# stm32-d40-platform.net
KiCad netlist of a schematic drawn in EAGLE
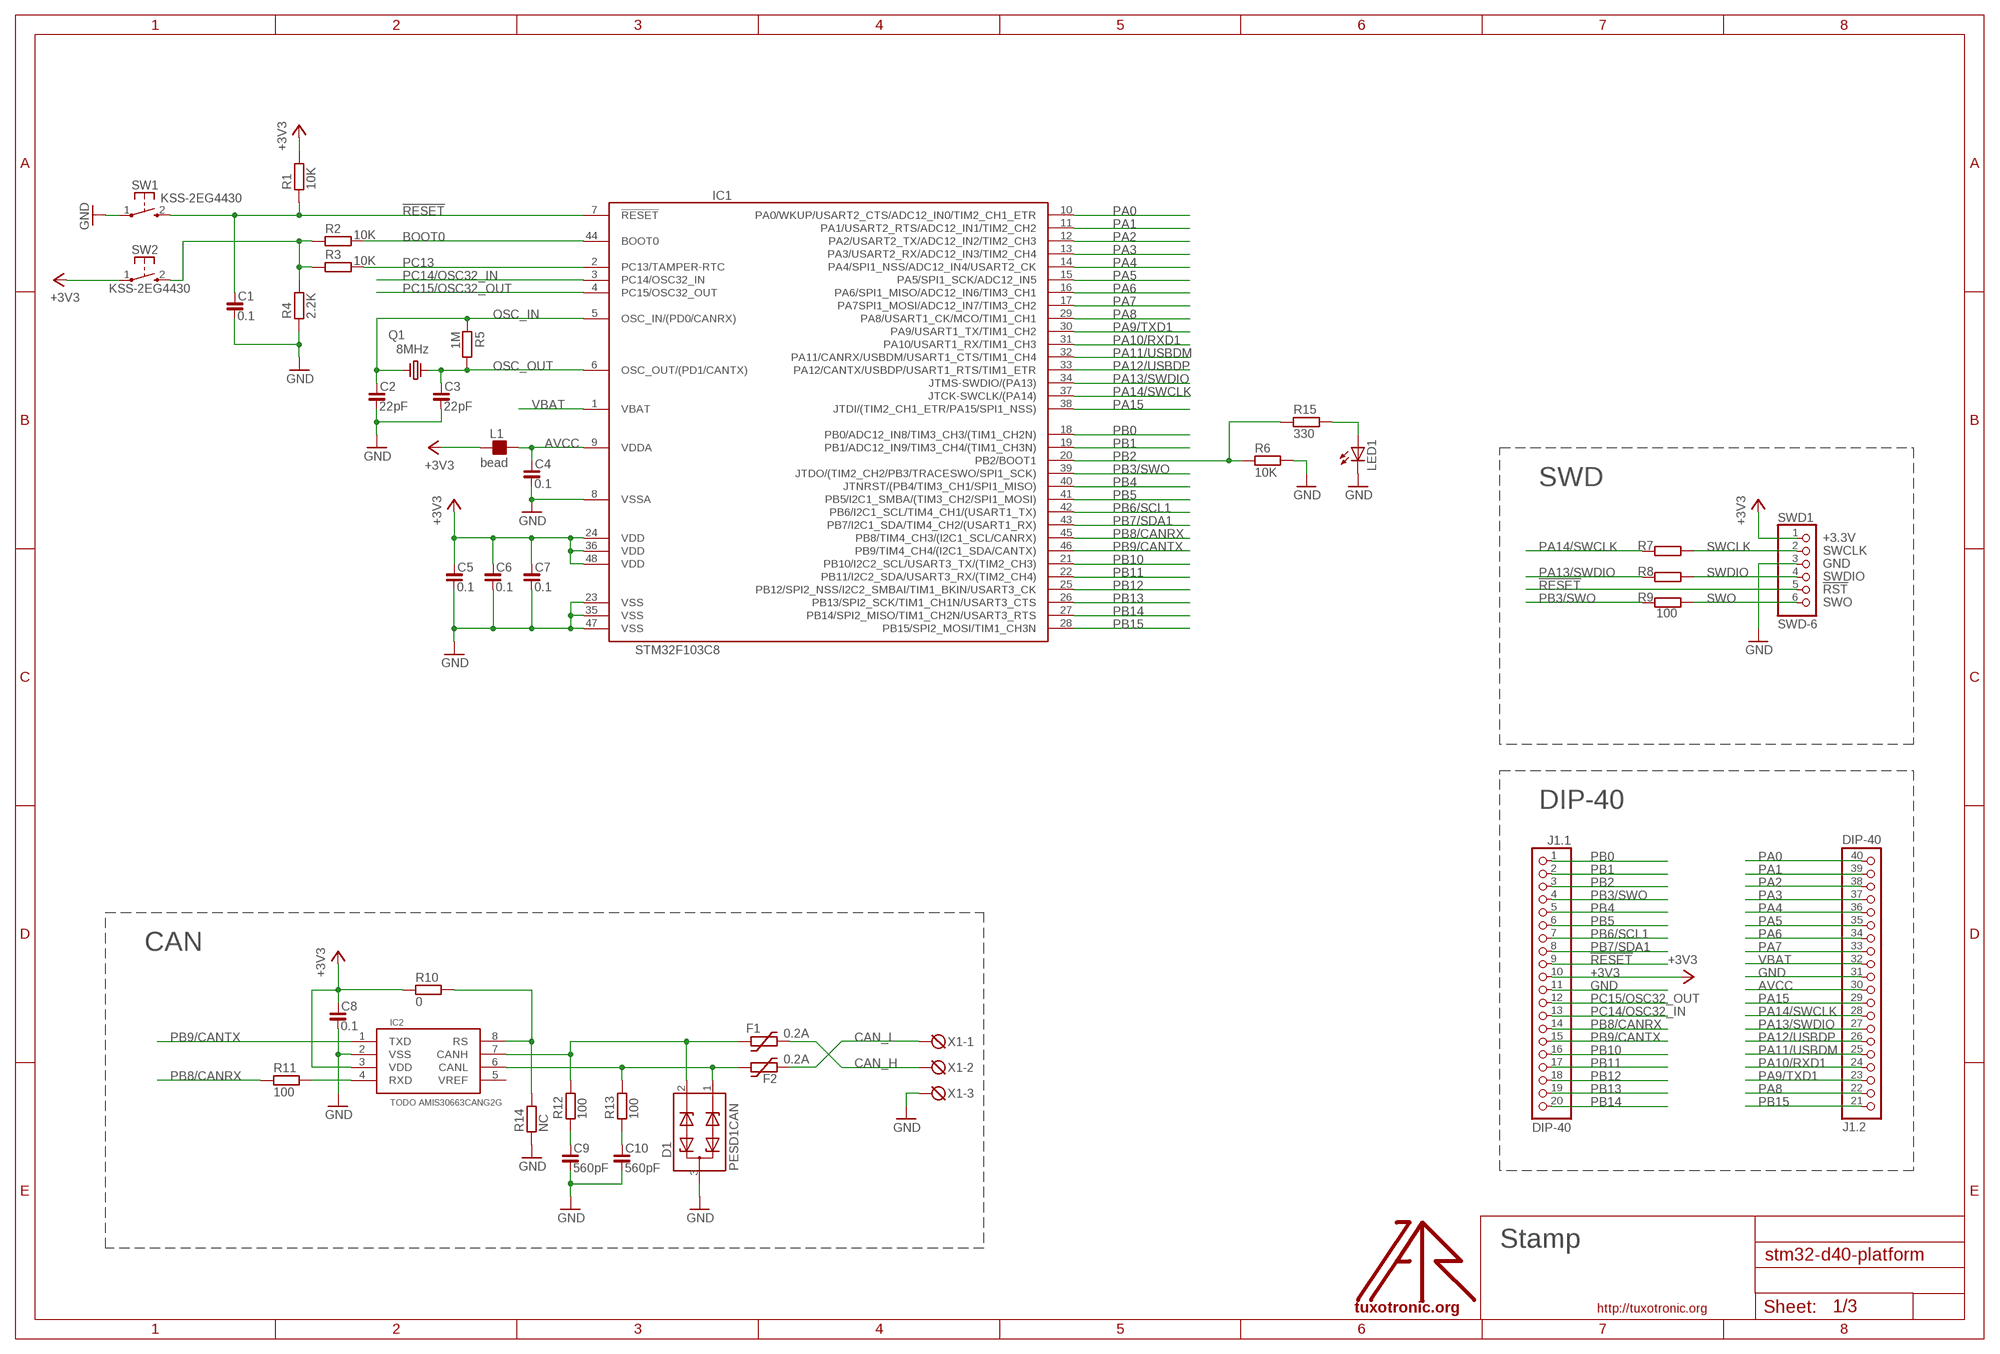
[diagram p0: schematic, sheet 1]
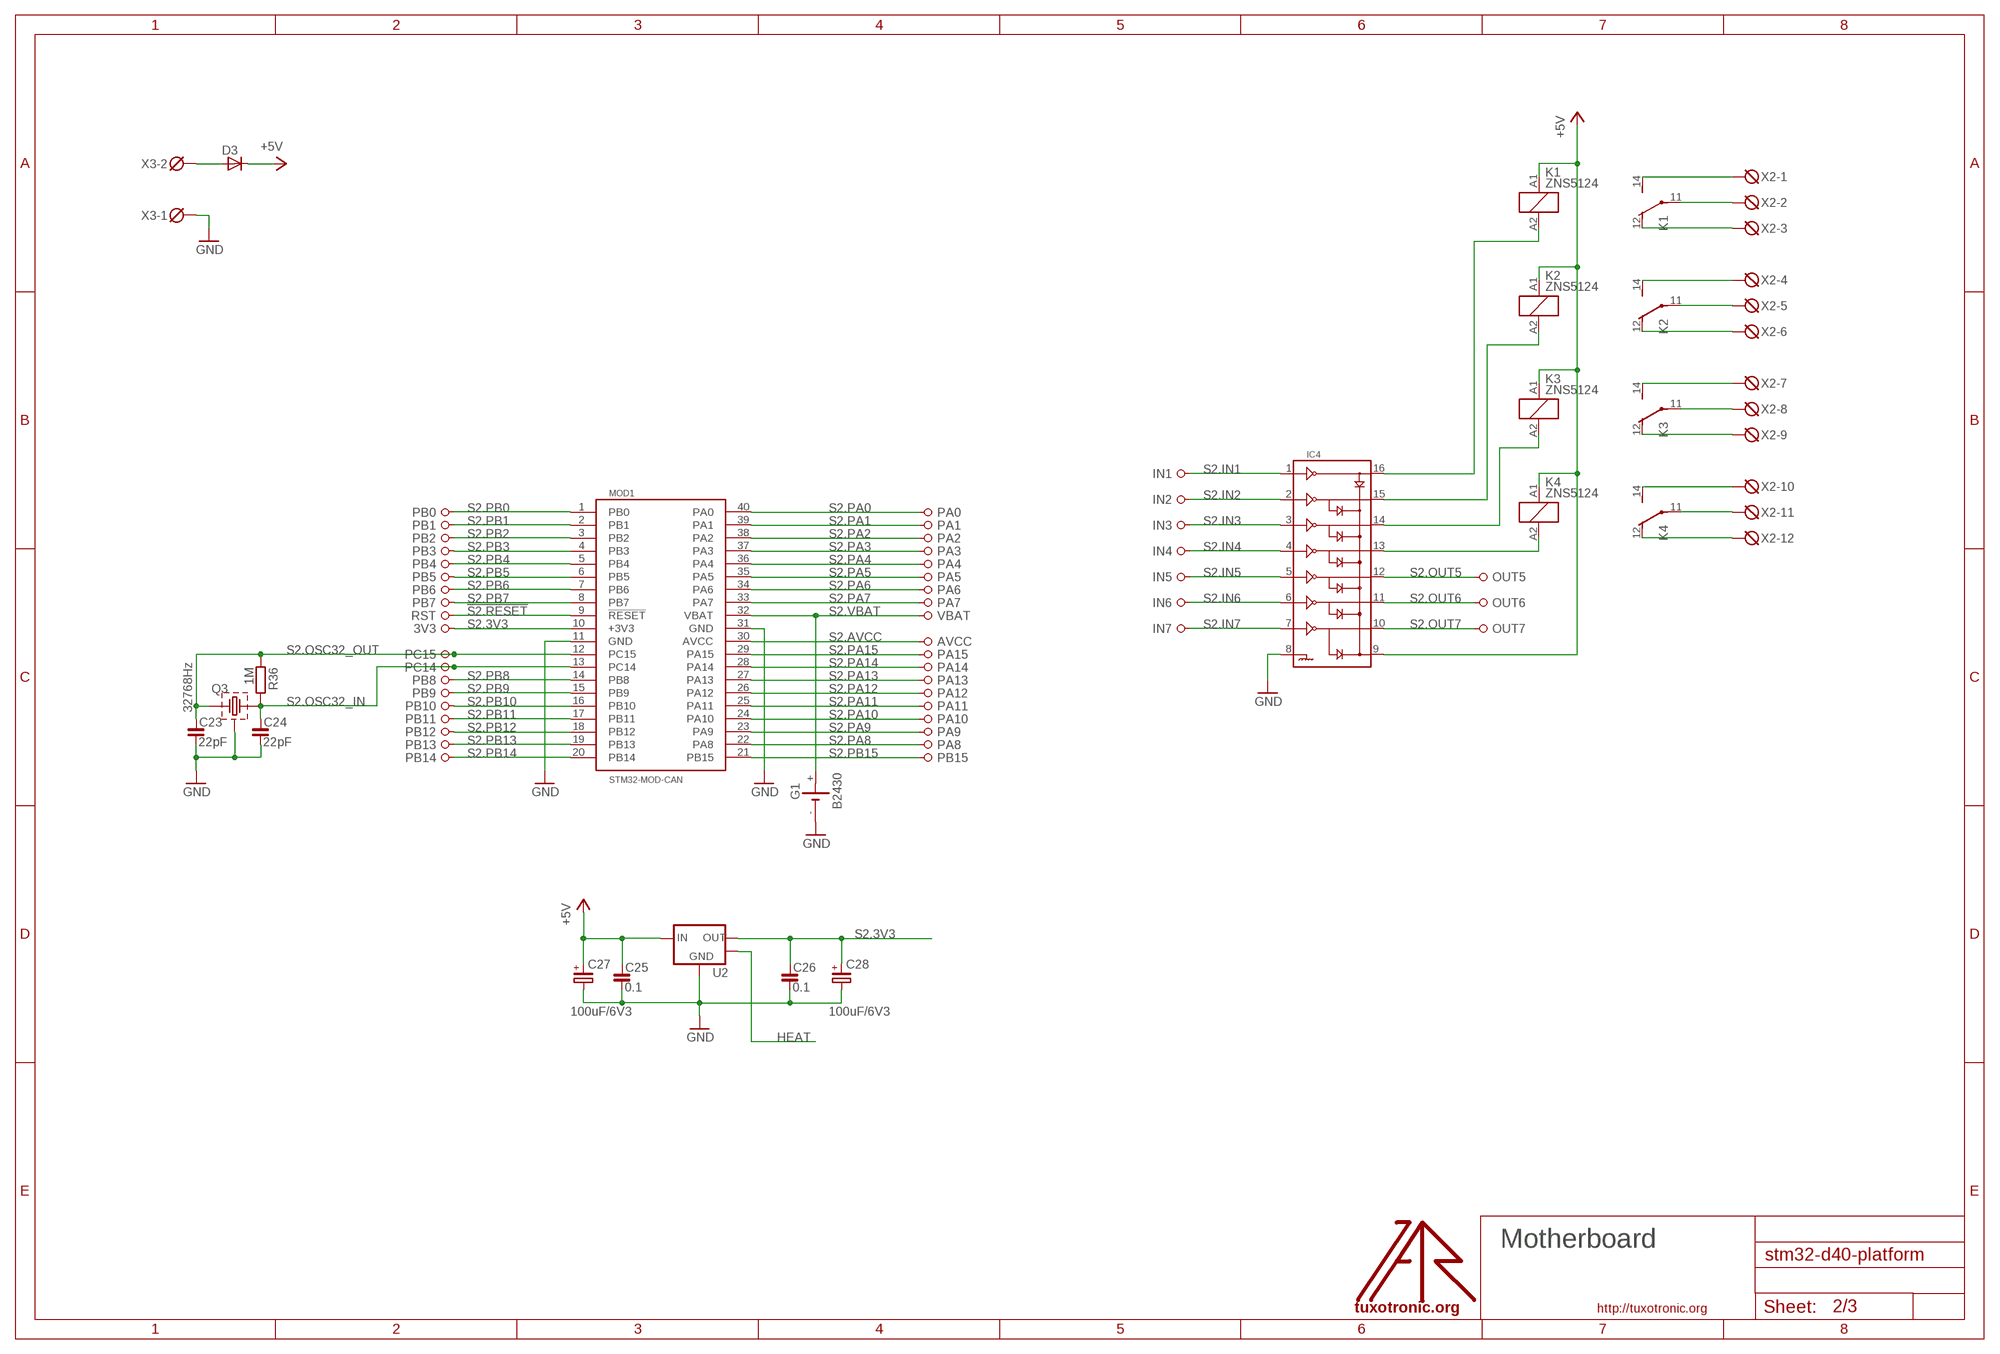
[diagram p1: schematic, sheet 2]
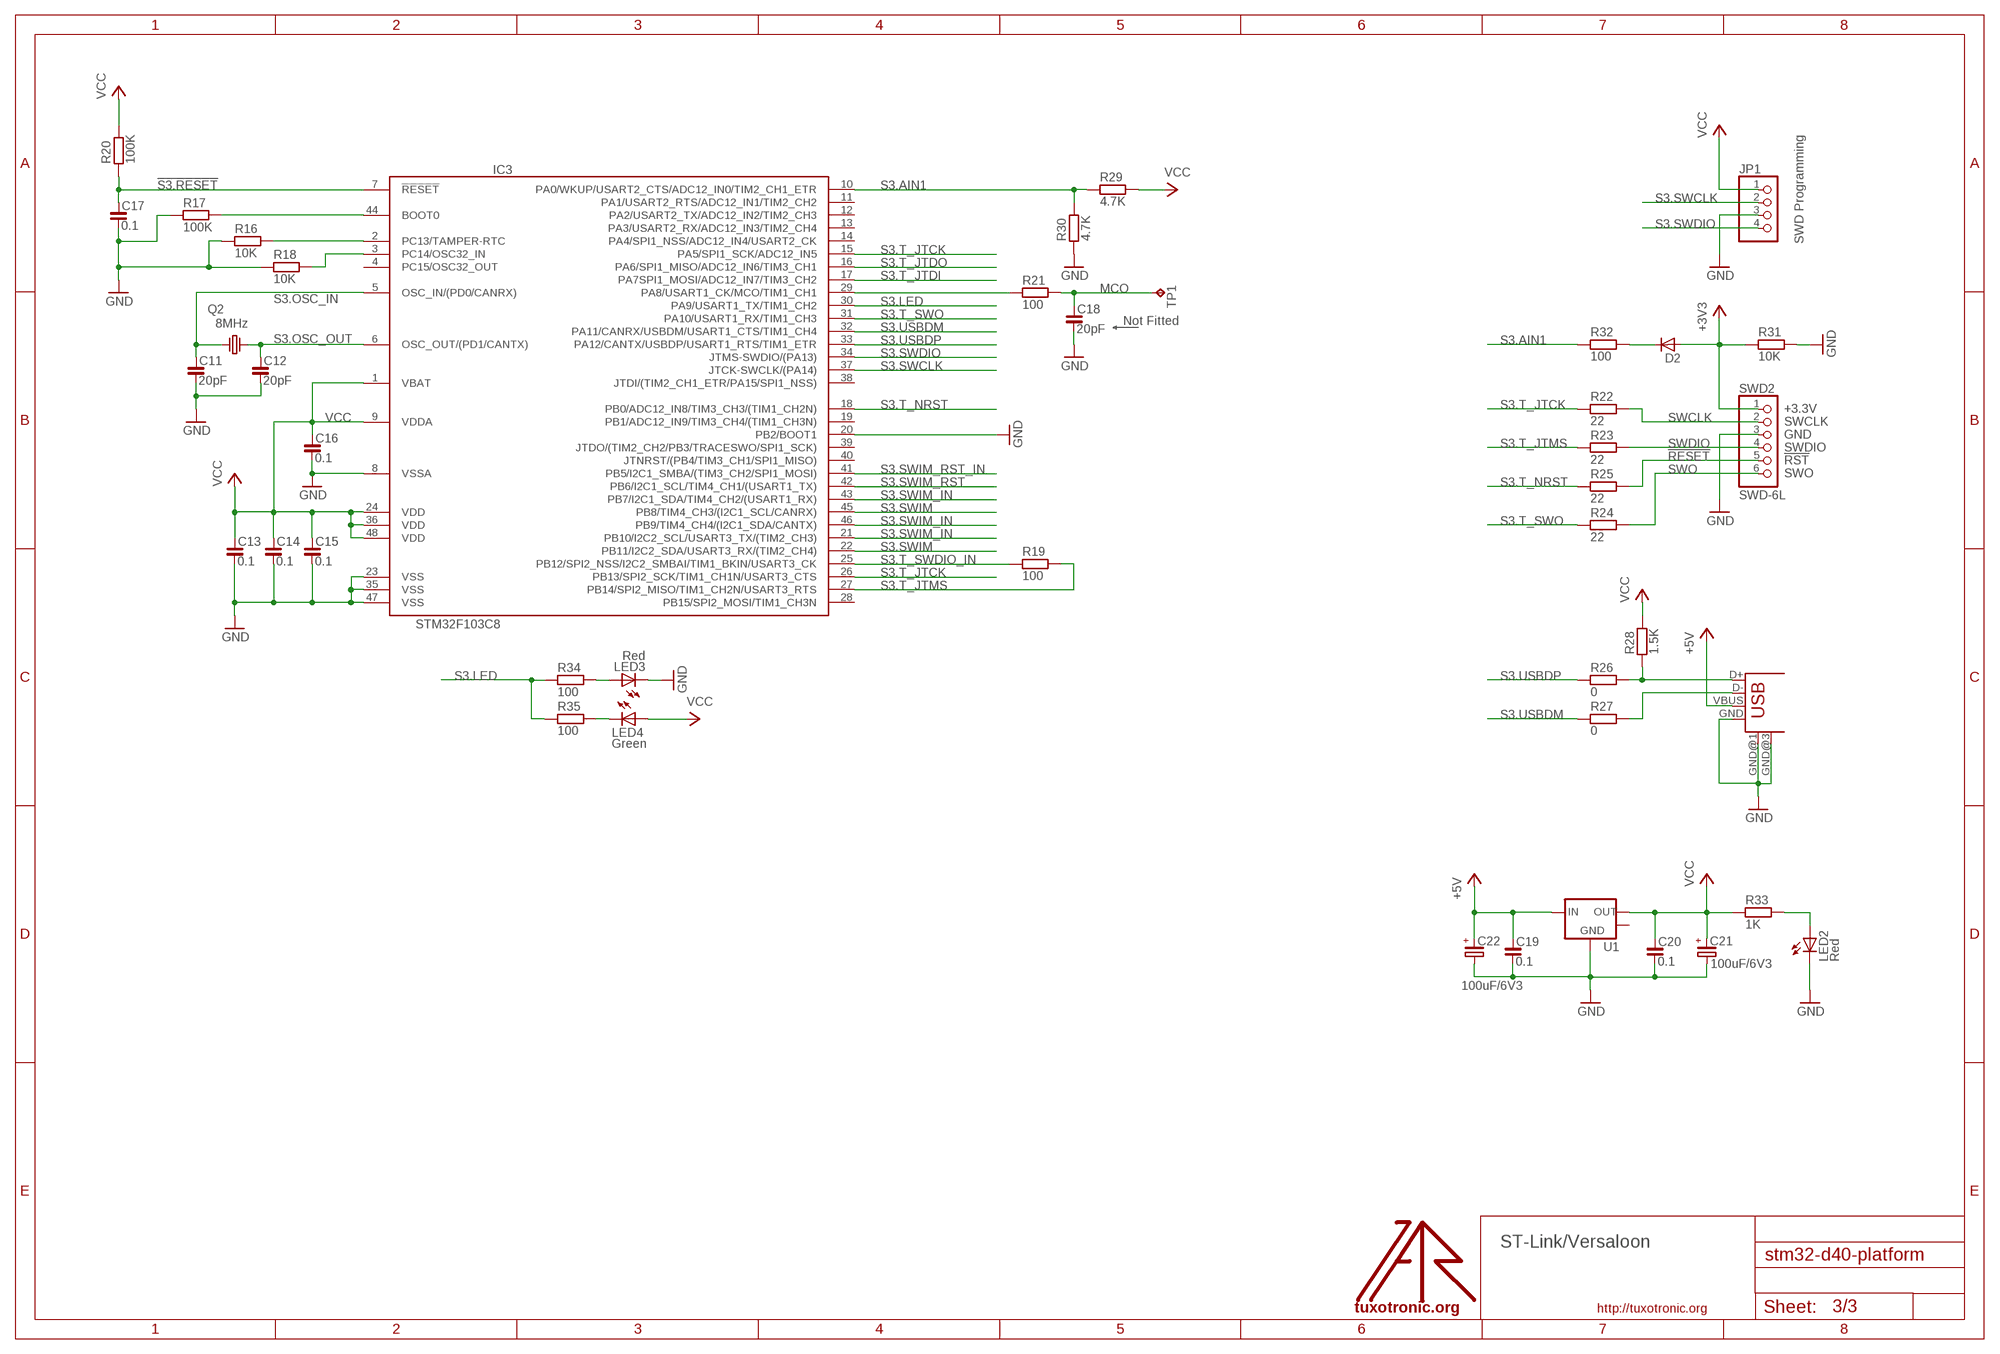
[diagram p2: schematic, sheet 3]

(export (version "E")
  (design (tool "Eeschema 10.0.6"))
  (components
    (comp (ref "C1")
      (value "0.1")
      (footprint "eagle-import:C0603")
      (libsource (lib "eagle-import") (part "C_0603"))
    )
    (comp (ref "C2")
      (value "22pF")
      (footprint "eagle-import:C0603")
      (libsource (lib "eagle-import") (part "C_0603"))
    )
    (comp (ref "C3")
      (value "22pF")
      (footprint "eagle-import:C0603")
      (libsource (lib "eagle-import") (part "C_0603"))
    )
    (comp (ref "C4")
      (value "0.1")
      (footprint "eagle-import:C0603")
      (libsource (lib "eagle-import") (part "C_0603"))
    )
    (comp (ref "C5")
      (value "0.1")
      (footprint "eagle-import:C0603")
      (libsource (lib "eagle-import") (part "C_0603"))
    )
    (comp (ref "C6")
      (value "0.1")
      (footprint "eagle-import:C0603")
      (libsource (lib "eagle-import") (part "C_0603"))
    )
    (comp (ref "C7")
      (value "0.1")
      (footprint "eagle-import:C0603")
      (libsource (lib "eagle-import") (part "C_0603"))
    )
    (comp (ref "C8")
      (value "0.1")
      (footprint "eagle-import:C0603")
      (libsource (lib "eagle-import") (part "C_0603"))
    )
    (comp (ref "C9")
      (value "560pF")
      (footprint "eagle-import:C0603")
      (libsource (lib "eagle-import") (part "C_0603"))
    )
    (comp (ref "C10")
      (value "560pF")
      (footprint "eagle-import:C0603")
      (libsource (lib "eagle-import") (part "C_0603"))
    )
    (comp (ref "D1")
      (value "PESD1CAN")
      (footprint "eagle-import:SOT23")
      (libsource (lib "eagle-import") (part "PESD1CAN"))
    )
    (comp (ref "F1")
      (value "0.2A")
      (footprint "eagle-import:1206L")
      (libsource (lib "eagle-import") (part "1206L"))
    )
    (comp (ref "F2")
      (value "0.2A")
      (footprint "eagle-import:1206L")
      (libsource (lib "eagle-import") (part "1206L"))
    )
    (comp (ref "IC1")
      (value "STM32F103C8")
      (footprint "eagle-import:LQFP48")
      (libsource (lib "eagle-import") (part "STM32F103C8"))
    )
    (comp (ref "IC2")
      (value "TODO AMIS30663CANG2G")
      (footprint "eagle-import:SO08")
      (libsource (lib "eagle-import") (part "SN65HVD230"))
    )
    (comp (ref "J1")
      (value "DIP-40")
      (footprint "eagle-import:DIP-40")
      (libsource (lib "eagle-import") (part "DIP-40"))
    )
    (comp (ref "L1")
      (value "bead")
      (footprint "eagle-import:L0603")
      (libsource (lib "eagle-import") (part "FB_0603"))
    )
    (comp (ref "LED1")
      (value "LEDCHIPLED_0603")
      (footprint "eagle-import:CHIPLED_0603")
      (libsource (lib "eagle-import") (part "LEDCHIPLED_0603"))
    )
    (comp (ref "Q1")
      (value "8MHz")
      (footprint "eagle-import:HC49_S")
      (libsource (lib "eagle-import") (part "CRYSTAL-HC49S"))
    )
    (comp (ref "R1")
      (value "10K")
      (footprint "eagle-import:R0603")
      (libsource (lib "eagle-import") (part "R_0603"))
    )
    (comp (ref "R2")
      (value "10K")
      (footprint "eagle-import:R0603")
      (libsource (lib "eagle-import") (part "R_0603"))
    )
    (comp (ref "R3")
      (value "10K")
      (footprint "eagle-import:R0603")
      (libsource (lib "eagle-import") (part "R_0603"))
    )
    (comp (ref "R4")
      (value "2.2K")
      (footprint "eagle-import:R0603")
      (libsource (lib "eagle-import") (part "R_0603"))
    )
    (comp (ref "R5")
      (value "1M")
      (footprint "eagle-import:R0603")
      (libsource (lib "eagle-import") (part "R_0603"))
    )
    (comp (ref "R6")
      (value "10K")
      (footprint "eagle-import:R0603")
      (libsource (lib "eagle-import") (part "R_0603"))
    )
    (comp (ref "R7")
      (value "100")
      (footprint "eagle-import:R0603")
      (libsource (lib "eagle-import") (part "R_0603"))
    )
    (comp (ref "R8")
      (value "100")
      (footprint "eagle-import:R0603")
      (libsource (lib "eagle-import") (part "R_0603"))
    )
    (comp (ref "R9")
      (value "100")
      (footprint "eagle-import:R0603")
      (libsource (lib "eagle-import") (part "R_0603"))
    )
    (comp (ref "R10")
      (value "0")
      (footprint "eagle-import:R0603")
      (libsource (lib "eagle-import") (part "R_0603"))
    )
    (comp (ref "R11")
      (value "100")
      (footprint "eagle-import:R0603")
      (libsource (lib "eagle-import") (part "R_0603"))
    )
    (comp (ref "R12")
      (value "100")
      (footprint "eagle-import:R0603")
      (libsource (lib "eagle-import") (part "R_0603"))
    )
    (comp (ref "R13")
      (value "100")
      (footprint "eagle-import:R0603")
      (libsource (lib "eagle-import") (part "R_0603"))
    )
    (comp (ref "R14")
      (value "NC")
      (footprint "eagle-import:R0603")
      (libsource (lib "eagle-import") (part "R_0603"))
    )
    (comp (ref "R15")
      (value "330")
      (footprint "eagle-import:R0603")
      (libsource (lib "eagle-import") (part "R_0603"))
    )
    (comp (ref "SW1")
      (value "KSS-2EG4430")
      (footprint "eagle-import:KSS-2EG4430")
      (libsource (lib "eagle-import") (part "KSS-2EG4430"))
    )
    (comp (ref "SW2")
      (value "KSS-2EG4430")
      (footprint "eagle-import:KSS-2EG4430")
      (libsource (lib "eagle-import") (part "KSS-2EG4430"))
    )
    (comp (ref "SWD1")
      (value "SWD-6")
      (footprint "eagle-import:JTAG6PIN")
      (libsource (lib "eagle-import") (part "SWD-6"))
    )
    (comp (ref "U$")
      (value "LOGO")
      (footprint "eagle-import:TT_LOGO")
      (libsource (lib "eagle-import") (part "LOGO"))
    )
    (comp (ref "X1")
      (value "DG3XX-03-3.5")
      (footprint "eagle-import:DG350-3.5-03P")
      (libsource (lib "eagle-import") (part "DG3XX-03-3.5"))
    )
    (comp (ref "3V3")
      (value "PIN-1X1_2.54")
      (footprint "eagle-import:1X01")
      (libsource (lib "eagle-import") (part "PIN-1X1_2.54"))
    )
    (comp (ref "AVCC")
      (value "PIN-1X1_2.54")
      (footprint "eagle-import:1X01")
      (libsource (lib "eagle-import") (part "PIN-1X1_2.54"))
    )
    (comp (ref "C23")
      (value "22pF")
      (footprint "eagle-import:C0805")
      (libsource (lib "eagle-import") (part "C_0805"))
    )
    (comp (ref "C24")
      (value "22pF")
      (footprint "eagle-import:C0805")
      (libsource (lib "eagle-import") (part "C_0805"))
    )
    (comp (ref "C25")
      (value "0.1")
      (footprint "eagle-import:C0805")
      (libsource (lib "eagle-import") (part "C_0805"))
    )
    (comp (ref "C26")
      (value "0.1")
      (footprint "eagle-import:C0805")
      (libsource (lib "eagle-import") (part "C_0805"))
    )
    (comp (ref "C27")
      (value "100uF/6V3")
      (footprint "eagle-import:CE-035X080")
      (libsource (lib "eagle-import") (part "CP_E-035X080"))
    )
    (comp (ref "C28")
      (value "100uF/6V3")
      (footprint "eagle-import:CE-035X080")
      (libsource (lib "eagle-import") (part "CP_E-035X080"))
    )
    (comp (ref "D3")
      (value "D-SMB")
      (footprint "eagle-import:SMB")
      (libsource (lib "eagle-import") (part "D-SMB"))
    )
    (comp (ref "G1")
      (value "B2430")
      (footprint "eagle-import:B2430")
      (libsource (lib "eagle-import") (part "B2430"))
    )
    (comp (ref "IC4")
      (value "ULN2003D")
      (footprint "eagle-import:SO16")
      (libsource (lib "eagle-import") (part "ULN2003D"))
    )
    (comp (ref "IN1")
      (value "PIN-1X1_2.54")
      (footprint "eagle-import:1X01")
      (libsource (lib "eagle-import") (part "PIN-1X1_2.54"))
    )
    (comp (ref "IN2")
      (value "PIN-1X1_2.54")
      (footprint "eagle-import:1X01")
      (libsource (lib "eagle-import") (part "PIN-1X1_2.54"))
    )
    (comp (ref "IN3")
      (value "PIN-1X1_2.54")
      (footprint "eagle-import:1X01")
      (libsource (lib "eagle-import") (part "PIN-1X1_2.54"))
    )
    (comp (ref "IN4")
      (value "PIN-1X1_2.54")
      (footprint "eagle-import:1X01")
      (libsource (lib "eagle-import") (part "PIN-1X1_2.54"))
    )
    (comp (ref "IN5")
      (value "PIN-1X1_2.54")
      (footprint "eagle-import:1X01")
      (libsource (lib "eagle-import") (part "PIN-1X1_2.54"))
    )
    (comp (ref "IN6")
      (value "PIN-1X1_2.54")
      (footprint "eagle-import:1X01")
      (libsource (lib "eagle-import") (part "PIN-1X1_2.54"))
    )
    (comp (ref "IN7")
      (value "PIN-1X1_2.54")
      (footprint "eagle-import:1X01")
      (libsource (lib "eagle-import") (part "PIN-1X1_2.54"))
    )
    (comp (ref "K1")
      (value "ZNS5124")
      (footprint "eagle-import:ZN5")
      (libsource (lib "eagle-import") (part "ZNS5124"))
    )
    (comp (ref "K2")
      (value "ZNS5124")
      (footprint "eagle-import:ZN5")
      (libsource (lib "eagle-import") (part "ZNS5124"))
    )
    (comp (ref "K3")
      (value "ZNS5124")
      (footprint "eagle-import:ZN5")
      (libsource (lib "eagle-import") (part "ZNS5124"))
    )
    (comp (ref "K4")
      (value "ZNS5124")
      (footprint "eagle-import:ZN5")
      (libsource (lib "eagle-import") (part "ZNS5124"))
    )
    (comp (ref "MOD1")
      (value "STM32-MOD-CAN")
      (footprint "eagle-import:DIL40")
      (libsource (lib "eagle-import") (part "STM32-MOD-CAN"))
    )
    (comp (ref "OUT5")
      (value "PIN-1X1_2.54")
      (footprint "eagle-import:1X01")
      (libsource (lib "eagle-import") (part "PIN-1X1_2.54"))
    )
    (comp (ref "OUT6")
      (value "PIN-1X1_2.54")
      (footprint "eagle-import:1X01")
      (libsource (lib "eagle-import") (part "PIN-1X1_2.54"))
    )
    (comp (ref "OUT7")
      (value "PIN-1X1_2.54")
      (footprint "eagle-import:1X01")
      (libsource (lib "eagle-import") (part "PIN-1X1_2.54"))
    )
    (comp (ref "PA0")
      (value "PIN-1X1_2.54")
      (footprint "eagle-import:1X01")
      (libsource (lib "eagle-import") (part "PIN-1X1_2.54"))
    )
    (comp (ref "PA1")
      (value "PIN-1X1_2.54")
      (footprint "eagle-import:1X01")
      (libsource (lib "eagle-import") (part "PIN-1X1_2.54"))
    )
    (comp (ref "PA2")
      (value "PIN-1X1_2.54")
      (footprint "eagle-import:1X01")
      (libsource (lib "eagle-import") (part "PIN-1X1_2.54"))
    )
    (comp (ref "PA3")
      (value "PIN-1X1_2.54")
      (footprint "eagle-import:1X01")
      (libsource (lib "eagle-import") (part "PIN-1X1_2.54"))
    )
    (comp (ref "PA4")
      (value "PIN-1X1_2.54")
      (footprint "eagle-import:1X01")
      (libsource (lib "eagle-import") (part "PIN-1X1_2.54"))
    )
    (comp (ref "PA5")
      (value "PIN-1X1_2.54")
      (footprint "eagle-import:1X01")
      (libsource (lib "eagle-import") (part "PIN-1X1_2.54"))
    )
    (comp (ref "PA6")
      (value "PIN-1X1_2.54")
      (footprint "eagle-import:1X01")
      (libsource (lib "eagle-import") (part "PIN-1X1_2.54"))
    )
    (comp (ref "PA7")
      (value "PIN-1X1_2.54")
      (footprint "eagle-import:1X01")
      (libsource (lib "eagle-import") (part "PIN-1X1_2.54"))
    )
    (comp (ref "PA8")
      (value "PIN-1X1_2.54")
      (footprint "eagle-import:1X01")
      (libsource (lib "eagle-import") (part "PIN-1X1_2.54"))
    )
    (comp (ref "PA9")
      (value "PIN-1X1_2.54")
      (footprint "eagle-import:1X01")
      (libsource (lib "eagle-import") (part "PIN-1X1_2.54"))
    )
    (comp (ref "PA10")
      (value "PIN-1X1_2.54")
      (footprint "eagle-import:1X01")
      (libsource (lib "eagle-import") (part "PIN-1X1_2.54"))
    )
    (comp (ref "PA11")
      (value "PIN-1X1_2.54")
      (footprint "eagle-import:1X01")
      (libsource (lib "eagle-import") (part "PIN-1X1_2.54"))
    )
    (comp (ref "PA12")
      (value "PIN-1X1_2.54")
      (footprint "eagle-import:1X01")
      (libsource (lib "eagle-import") (part "PIN-1X1_2.54"))
    )
    (comp (ref "PA13")
      (value "PIN-1X1_2.54")
      (footprint "eagle-import:1X01")
      (libsource (lib "eagle-import") (part "PIN-1X1_2.54"))
    )
    (comp (ref "PA14")
      (value "PIN-1X1_2.54")
      (footprint "eagle-import:1X01")
      (libsource (lib "eagle-import") (part "PIN-1X1_2.54"))
    )
    (comp (ref "PA15")
      (value "PIN-1X1_2.54")
      (footprint "eagle-import:1X01")
      (libsource (lib "eagle-import") (part "PIN-1X1_2.54"))
    )
    (comp (ref "PB0")
      (value "PIN-1X1_2.54")
      (footprint "eagle-import:1X01")
      (libsource (lib "eagle-import") (part "PIN-1X1_2.54"))
    )
    (comp (ref "PB1")
      (value "PIN-1X1_2.54")
      (footprint "eagle-import:1X01")
      (libsource (lib "eagle-import") (part "PIN-1X1_2.54"))
    )
    (comp (ref "PB2")
      (value "PIN-1X1_2.54")
      (footprint "eagle-import:1X01")
      (libsource (lib "eagle-import") (part "PIN-1X1_2.54"))
    )
    (comp (ref "PB3")
      (value "PIN-1X1_2.54")
      (footprint "eagle-import:1X01")
      (libsource (lib "eagle-import") (part "PIN-1X1_2.54"))
    )
    (comp (ref "PB4")
      (value "PIN-1X1_2.54")
      (footprint "eagle-import:1X01")
      (libsource (lib "eagle-import") (part "PIN-1X1_2.54"))
    )
    (comp (ref "PB5")
      (value "PIN-1X1_2.54")
      (footprint "eagle-import:1X01")
      (libsource (lib "eagle-import") (part "PIN-1X1_2.54"))
    )
    (comp (ref "PB6")
      (value "PIN-1X1_2.54")
      (footprint "eagle-import:1X01")
      (libsource (lib "eagle-import") (part "PIN-1X1_2.54"))
    )
    (comp (ref "PB7")
      (value "PIN-1X1_2.54")
      (footprint "eagle-import:1X01")
      (libsource (lib "eagle-import") (part "PIN-1X1_2.54"))
    )
    (comp (ref "PB8")
      (value "PIN-1X1_2.54")
      (footprint "eagle-import:1X01")
      (libsource (lib "eagle-import") (part "PIN-1X1_2.54"))
    )
    (comp (ref "PB9")
      (value "PIN-1X1_2.54")
      (footprint "eagle-import:1X01")
      (libsource (lib "eagle-import") (part "PIN-1X1_2.54"))
    )
    (comp (ref "PB10")
      (value "PIN-1X1_2.54")
      (footprint "eagle-import:1X01")
      (libsource (lib "eagle-import") (part "PIN-1X1_2.54"))
    )
    (comp (ref "PB11")
      (value "PIN-1X1_2.54")
      (footprint "eagle-import:1X01")
      (libsource (lib "eagle-import") (part "PIN-1X1_2.54"))
    )
    (comp (ref "PB12")
      (value "PIN-1X1_2.54")
      (footprint "eagle-import:1X01")
      (libsource (lib "eagle-import") (part "PIN-1X1_2.54"))
    )
    (comp (ref "PB13")
      (value "PIN-1X1_2.54")
      (footprint "eagle-import:1X01")
      (libsource (lib "eagle-import") (part "PIN-1X1_2.54"))
    )
    (comp (ref "PB14")
      (value "PIN-1X1_2.54")
      (footprint "eagle-import:1X01")
      (libsource (lib "eagle-import") (part "PIN-1X1_2.54"))
    )
    (comp (ref "PB15")
      (value "PIN-1X1_2.54")
      (footprint "eagle-import:1X01")
      (libsource (lib "eagle-import") (part "PIN-1X1_2.54"))
    )
    (comp (ref "PC14")
      (value "PIN-1X1_2.54")
      (footprint "eagle-import:1X01")
      (libsource (lib "eagle-import") (part "PIN-1X1_2.54"))
    )
    (comp (ref "PC15")
      (value "PIN-1X1_2.54")
      (footprint "eagle-import:1X01")
      (libsource (lib "eagle-import") (part "PIN-1X1_2.54"))
    )
    (comp (ref "Q3")
      (value "32768Hz")
      (footprint "eagle-import:TC38H-G")
      (libsource (lib "eagle-import") (part "CRSTL3-"))
    )
    (comp (ref "R36")
      (value "1M")
      (footprint "eagle-import:R0805")
      (libsource (lib "eagle-import") (part "R_0805"))
    )
    (comp (ref "RST")
      (value "PIN-1X1_2.54")
      (footprint "eagle-import:1X01")
      (libsource (lib "eagle-import") (part "PIN-1X1_2.54"))
    )
    (comp (ref "U$1")
      (value "LOGO")
      (footprint "eagle-import:TT_LOGO")
      (libsource (lib "eagle-import") (part "LOGO"))
    )
    (comp (ref "U2")
      (value "LM1117-3.3")
      (footprint "eagle-import:SOT223")
      (libsource (lib "eagle-import") (part "LM1117-3.3"))
    )
    (comp (ref "VBAT")
      (value "PIN-1X1_2.54")
      (footprint "eagle-import:1X01")
      (libsource (lib "eagle-import") (part "PIN-1X1_2.54"))
    )
    (comp (ref "X2")
      (value "DG3XX-12-5.0")
      (footprint "eagle-import:DG306-5.0-12P")
      (libsource (lib "eagle-import") (part "DG3XX-12-5.0"))
    )
    (comp (ref "X3")
      (value "DG3XX-02-5.0")
      (footprint "eagle-import:DG306-5.0-02P")
      (libsource (lib "eagle-import") (part "DG3XX-02-5.0"))
    )
    (comp (ref "C11")
      (value "20pF")
      (footprint "eagle-import:C0603")
      (libsource (lib "eagle-import") (part "C_0603"))
    )
    (comp (ref "C12")
      (value "20pF")
      (footprint "eagle-import:C0603")
      (libsource (lib "eagle-import") (part "C_0603"))
    )
    (comp (ref "C13")
      (value "0.1")
      (footprint "eagle-import:C0603")
      (libsource (lib "eagle-import") (part "C_0603"))
    )
    (comp (ref "C14")
      (value "0.1")
      (footprint "eagle-import:C0603")
      (libsource (lib "eagle-import") (part "C_0603"))
    )
    (comp (ref "C15")
      (value "0.1")
      (footprint "eagle-import:C0603")
      (libsource (lib "eagle-import") (part "C_0603"))
    )
    (comp (ref "C16")
      (value "0.1")
      (footprint "eagle-import:C0603")
      (libsource (lib "eagle-import") (part "C_0603"))
    )
    (comp (ref "C17")
      (value "0.1")
      (footprint "eagle-import:C0603")
      (libsource (lib "eagle-import") (part "C_0603"))
    )
    (comp (ref "C18")
      (value "20pF")
      (footprint "eagle-import:C0603")
      (libsource (lib "eagle-import") (part "C_0603"))
    )
    (comp (ref "C19")
      (value "0.1")
      (footprint "eagle-import:C0603")
      (libsource (lib "eagle-import") (part "C_0603"))
    )
    (comp (ref "C20")
      (value "0.1")
      (footprint "eagle-import:C0603")
      (libsource (lib "eagle-import") (part "C_0603"))
    )
    (comp (ref "C21")
      (value "100uF/6V3")
      (footprint "eagle-import:SMC_C")
      (libsource (lib "eagle-import") (part "CP_SMCC"))
    )
    (comp (ref "C22")
      (value "100uF/6V3")
      (footprint "eagle-import:SMC_C")
      (libsource (lib "eagle-import") (part "CP_SMCC"))
    )
    (comp (ref "D2")
      (value "BAT54A1-C3")
      (footprint "eagle-import:SOT23")
      (libsource (lib "eagle-import") (part "BAT54A1-C3"))
    )
    (comp (ref "IC3")
      (value "STM32F103C8")
      (footprint "eagle-import:LQFP48")
      (libsource (lib "eagle-import") (part "STM32F103C8"))
    )
    (comp (ref "JP1")
      (value "PINHD-1X4_2.00")
      (footprint "eagle-import:1X04M")
      (libsource (lib "eagle-import") (part "PINHD-1X4_2.00"))
    )
    (comp (ref "LED2")
      (value "Red")
      (footprint "eagle-import:CHIPLED_0603")
      (libsource (lib "eagle-import") (part "LEDCHIPLED_0603"))
    )
    (comp (ref "LED3")
      (value "Red")
      (footprint "eagle-import:CHIPLED_0603")
      (libsource (lib "eagle-import") (part "LEDCHIPLED_0603"))
    )
    (comp (ref "LED4")
      (value "Green")
      (footprint "eagle-import:CHIPLED_0603")
      (libsource (lib "eagle-import") (part "LEDCHIPLED_0603"))
    )
    (comp (ref "Q2")
      (value "8MHz")
      (footprint "eagle-import:HC49_S")
      (libsource (lib "eagle-import") (part "CRYSTAL-HC49S"))
    )
    (comp (ref "R16")
      (value "10K")
      (footprint "eagle-import:R0603")
      (libsource (lib "eagle-import") (part "R_0603"))
    )
    (comp (ref "R17")
      (value "100K")
      (footprint "eagle-import:R0603")
      (libsource (lib "eagle-import") (part "R_0603"))
    )
    (comp (ref "R18")
      (value "10K")
      (footprint "eagle-import:R0603")
      (libsource (lib "eagle-import") (part "R_0603"))
    )
    (comp (ref "R19")
      (value "100")
      (footprint "eagle-import:R0603")
      (libsource (lib "eagle-import") (part "R_0603"))
    )
    (comp (ref "R20")
      (value "100K")
      (footprint "eagle-import:R0603")
      (libsource (lib "eagle-import") (part "R_0603"))
    )
    (comp (ref "R21")
      (value "100")
      (footprint "eagle-import:R0603")
      (libsource (lib "eagle-import") (part "R_0603"))
    )
    (comp (ref "R22")
      (value "22")
      (footprint "eagle-import:R0603")
      (libsource (lib "eagle-import") (part "R_0603"))
    )
    (comp (ref "R23")
      (value "22")
      (footprint "eagle-import:R0603")
      (libsource (lib "eagle-import") (part "R_0603"))
    )
    (comp (ref "R24")
      (value "22")
      (footprint "eagle-import:R0603")
      (libsource (lib "eagle-import") (part "R_0603"))
    )
    (comp (ref "R25")
      (value "22")
      (footprint "eagle-import:R0603")
      (libsource (lib "eagle-import") (part "R_0603"))
    )
    (comp (ref "R26")
      (value "0")
      (footprint "eagle-import:R0603")
      (libsource (lib "eagle-import") (part "R_0603"))
    )
    (comp (ref "R27")
      (value "0")
      (footprint "eagle-import:R0603")
      (libsource (lib "eagle-import") (part "R_0603"))
    )
    (comp (ref "R28")
      (value "1.5K")
      (footprint "eagle-import:R0603")
      (libsource (lib "eagle-import") (part "R_0603"))
    )
    (comp (ref "R29")
      (value "4.7K")
      (footprint "eagle-import:R0603")
      (libsource (lib "eagle-import") (part "R_0603"))
    )
    (comp (ref "R30")
      (value "4.7K")
      (footprint "eagle-import:R0603")
      (libsource (lib "eagle-import") (part "R_0603"))
    )
    (comp (ref "R31")
      (value "10K")
      (footprint "eagle-import:R0603")
      (libsource (lib "eagle-import") (part "R_0603"))
    )
    (comp (ref "R32")
      (value "100")
      (footprint "eagle-import:R0603")
      (libsource (lib "eagle-import") (part "R_0603"))
    )
    (comp (ref "R33")
      (value "1K")
      (footprint "eagle-import:R0603")
      (libsource (lib "eagle-import") (part "R_0603"))
    )
    (comp (ref "R34")
      (value "100")
      (footprint "eagle-import:R0603")
      (libsource (lib "eagle-import") (part "R_0603"))
    )
    (comp (ref "R35")
      (value "100")
      (footprint "eagle-import:R0603")
      (libsource (lib "eagle-import") (part "R_0603"))
    )
    (comp (ref "S3.LOGO")
      (value "LOGO")
      (footprint "eagle-import:TT_LOGO")
      (libsource (lib "eagle-import") (part "LOGO"))
    )
    (comp (ref "SWD2")
      (value "SWD-6L")
      (footprint "eagle-import:SWD6PIN_L")
      (libsource (lib "eagle-import") (part "SWD-6L"))
    )
    (comp (ref "TP1")
      (value "TPB1,27")
      (footprint "eagle-import:B1,27")
      (libsource (lib "eagle-import") (part "TPB1,27"))
    )
    (comp (ref "U1")
      (value "LM1117-3.3")
      (footprint "eagle-import:SOT223")
      (libsource (lib "eagle-import") (part "LM1117-3.3"))
    )
    (comp (ref "USB1")
      (value "USB-MB-S2")
      (footprint "eagle-import:USB-MB-S2")
      (libsource (lib "eagle-import") (part "USB-MB-S2"))
    )
  )
  (nets
    (net (code "1") (name "+3V3") (class "Default")
      (node (ref "C5") (pin "1") (pinfunction "1_1") (pintype "passive"))
      (node (ref "C6") (pin "1") (pinfunction "1_1") (pintype "passive"))
      (node (ref "C7") (pin "1") (pinfunction "1_1") (pintype "passive"))
      (node (ref "C8") (pin "1") (pinfunction "1_1") (pintype "passive"))
      (node (ref "D2") (pin "1") (pinfunction "A_1") (pintype "passive"))
      (node (ref "IC1") (pin "24") (pinfunction "VDD_24") (pintype "power_in"))
      (node (ref "IC1") (pin "36") (pinfunction "VDD_36") (pintype "power_in"))
      (node (ref "IC1") (pin "48") (pinfunction "VDD_48") (pintype "power_in"))
      (node (ref "IC2") (pin "3") (pinfunction "VDD_3") (pintype "power_in"))
      (node (ref "J1") (pin "10") (pinfunction "10_10") (pintype "passive"))
      (node (ref "L1") (pin "1") (pinfunction "1_1") (pintype "passive"))
      (node (ref "R1") (pin "2") (pinfunction "2_2") (pintype "passive"))
      (node (ref "R10") (pin "1") (pinfunction "1_1") (pintype "passive"))
      (node (ref "R31") (pin "1") (pinfunction "1_1") (pintype "passive"))
      (node (ref "SW2") (pin "1") (pinfunction "P_1") (pintype "passive"))
      (node (ref "SWD1") (pin "1") (pinfunction "1_1") (pintype "passive"))
      (node (ref "SWD2") (pin "1") (pinfunction "1_1") (pintype "passive"))
    )
    (net (code "2") (name "+5V") (class "Default")
      (node (ref "C19") (pin "1") (pinfunction "1_1") (pintype "passive"))
      (node (ref "C22") (pin "+") (pinfunction "+_+") (pintype "passive"))
      (node (ref "C25") (pin "1") (pinfunction "1_1") (pintype "passive"))
      (node (ref "C27") (pin "+") (pinfunction "+_+") (pintype "passive"))
      (node (ref "D3") (pin "C") (pinfunction "C_C") (pintype "passive"))
      (node (ref "IC4") (pin "9") (pinfunction "9_9") (pintype "power_in"))
      (node (ref "K1") (pin "A1") (pinfunction "1_A1") (pintype "passive"))
      (node (ref "K2") (pin "A1") (pinfunction "1_A1") (pintype "passive"))
      (node (ref "K3") (pin "A1") (pinfunction "1_A1") (pintype "passive"))
      (node (ref "K4") (pin "A1") (pinfunction "1_A1") (pintype "passive"))
      (node (ref "U1") (pin "3") (pinfunction "IN_3") (pintype "power_in"))
      (node (ref "U2") (pin "3") (pinfunction "IN_3") (pintype "power_in"))
      (node (ref "USB1") (pin "VBUS") (pinfunction "VBUS_VBUS") (pintype "bidirectional"))
    )
    (net (code "3") (name "AVCC") (class "Default")
      (node (ref "C4") (pin "1") (pinfunction "1_1") (pintype "passive"))
      (node (ref "IC1") (pin "9") (pinfunction "VDDA_9") (pintype "power_in"))
      (node (ref "J1") (pin "30") (pinfunction "10_30") (pintype "passive"))
      (node (ref "L1") (pin "2") (pinfunction "2_2") (pintype "passive"))
    )
    (net (code "4") (name "BOOT0") (class "Default")
      (node (ref "IC1") (pin "44") (pinfunction "BOOT0_44") (pintype "input"))
      (node (ref "R2") (pin "2") (pinfunction "2_2") (pintype "passive"))
    )
    (net (code "5") (name "CAN_H") (class "Default")
      (node (ref "F1") (pin "P$2") (pinfunction "2_P$2") (pintype "passive"))
      (node (ref "X1") (pin "2") (pinfunction "KL_2") (pintype "passive"))
    )
    (net (code "6") (name "CAN_L") (class "Default")
      (node (ref "F2") (pin "P$2") (pinfunction "2_P$2") (pintype "passive"))
      (node (ref "X1") (pin "1") (pinfunction "KL_1") (pintype "passive"))
    )
    (net (code "7") (name "GND") (class "Default")
      (node (ref "C1") (pin "2") (pinfunction "2_2") (pintype "passive"))
      (node (ref "C10") (pin "2") (pinfunction "2_2") (pintype "passive"))
      (node (ref "C11") (pin "2") (pinfunction "2_2") (pintype "passive"))
      (node (ref "C12") (pin "2") (pinfunction "2_2") (pintype "passive"))
      (node (ref "C13") (pin "2") (pinfunction "2_2") (pintype "passive"))
      (node (ref "C14") (pin "2") (pinfunction "2_2") (pintype "passive"))
      (node (ref "C15") (pin "2") (pinfunction "2_2") (pintype "passive"))
      (node (ref "C16") (pin "2") (pinfunction "2_2") (pintype "passive"))
      (node (ref "C17") (pin "2") (pinfunction "2_2") (pintype "passive"))
      (node (ref "C18") (pin "2") (pinfunction "2_2") (pintype "passive"))
      (node (ref "C19") (pin "2") (pinfunction "2_2") (pintype "passive"))
      (node (ref "C2") (pin "2") (pinfunction "2_2") (pintype "passive"))
      (node (ref "C20") (pin "2") (pinfunction "2_2") (pintype "passive"))
      (node (ref "C21") (pin "-") (pinfunction "-_-") (pintype "passive"))
      (node (ref "C22") (pin "-") (pinfunction "-_-") (pintype "passive"))
      (node (ref "C23") (pin "2") (pinfunction "2_2") (pintype "passive"))
      (node (ref "C24") (pin "2") (pinfunction "2_2") (pintype "passive"))
      (node (ref "C25") (pin "2") (pinfunction "2_2") (pintype "passive"))
      (node (ref "C26") (pin "2") (pinfunction "2_2") (pintype "passive"))
      (node (ref "C27") (pin "-") (pinfunction "-_-") (pintype "passive"))
      (node (ref "C28") (pin "-") (pinfunction "-_-") (pintype "passive"))
      (node (ref "C3") (pin "2") (pinfunction "2_2") (pintype "passive"))
      (node (ref "C4") (pin "2") (pinfunction "2_2") (pintype "passive"))
      (node (ref "C5") (pin "2") (pinfunction "2_2") (pintype "passive"))
      (node (ref "C6") (pin "2") (pinfunction "2_2") (pintype "passive"))
      (node (ref "C7") (pin "2") (pinfunction "2_2") (pintype "passive"))
      (node (ref "C8") (pin "2") (pinfunction "2_2") (pintype "passive"))
      (node (ref "C9") (pin "2") (pinfunction "2_2") (pintype "passive"))
      (node (ref "D1") (pin "3") (pinfunction "3_3") (pintype "passive"))
      (node (ref "G1") (pin "-") (pinfunction "-_-") (pintype "passive"))
      (node (ref "IC1") (pin "23") (pinfunction "VSS_23") (pintype "power_in"))
      (node (ref "IC1") (pin "35") (pinfunction "VSS_35") (pintype "power_in"))
      (node (ref "IC1") (pin "47") (pinfunction "VSS_47") (pintype "power_in"))
      (node (ref "IC1") (pin "8") (pinfunction "VSSA_8") (pintype "power_in"))
      (node (ref "IC2") (pin "2") (pinfunction "VSS_2") (pintype "power_in"))
      (node (ref "IC3") (pin "20") (pinfunction "PB2/BOOT1_20") (pintype "bidirectional"))
      (node (ref "IC3") (pin "23") (pinfunction "VSS_23") (pintype "power_in"))
      (node (ref "IC3") (pin "35") (pinfunction "VSS_35") (pintype "power_in"))
      (node (ref "IC3") (pin "47") (pinfunction "VSS_47") (pintype "power_in"))
      (node (ref "IC3") (pin "8") (pinfunction "VSSA_8") (pintype "power_in"))
      (node (ref "IC4") (pin "8") (pinfunction "8_8") (pintype "power_in"))
      (node (ref "J1") (pin "11") (pinfunction "11_11") (pintype "passive"))
      (node (ref "J1") (pin "31") (pinfunction "11_31") (pintype "passive"))
      (node (ref "JP1") (pin "3") (pinfunction "3_3") (pintype "passive"))
      (node (ref "LED1") (pin "C") (pinfunction "C_C") (pintype "passive"))
      (node (ref "LED2") (pin "C") (pinfunction "C_C") (pintype "passive"))
      (node (ref "LED3") (pin "C") (pinfunction "C_C") (pintype "passive"))
      (node (ref "MOD1") (pin "11") (pinfunction "GND_11") (pintype "power_in"))
      (node (ref "MOD1") (pin "31") (pinfunction "GND_31") (pintype "power_in"))
      (node (ref "Q3") (pin "GND") (pinfunction "P$1_GND") (pintype "passive"))
      (node (ref "R14") (pin "1") (pinfunction "1_1") (pintype "passive"))
      (node (ref "R16") (pin "1") (pinfunction "1_1") (pintype "passive"))
      (node (ref "R17") (pin "1") (pinfunction "1_1") (pintype "passive"))
      (node (ref "R18") (pin "1") (pinfunction "1_1") (pintype "passive"))
      (node (ref "R30") (pin "1") (pinfunction "1_1") (pintype "passive"))
      (node (ref "R31") (pin "2") (pinfunction "2_2") (pintype "passive"))
      (node (ref "R4") (pin "1") (pinfunction "1_1") (pintype "passive"))
      (node (ref "R6") (pin "2") (pinfunction "2_2") (pintype "passive"))
      (node (ref "SW1") (pin "1") (pinfunction "P_1") (pintype "passive"))
      (node (ref "SWD1") (pin "3") (pinfunction "3_3") (pintype "passive"))
      (node (ref "SWD2") (pin "3") (pinfunction "3_3") (pintype "passive"))
      (node (ref "U1") (pin "1") (pinfunction "GND_1") (pintype "power_in"))
      (node (ref "U2") (pin "1") (pinfunction "GND_1") (pintype "power_in"))
      (node (ref "USB1") (pin "GND") (pinfunction "GND_GND") (pintype "bidirectional"))
      (node (ref "USB1") (pin "GND@1") (pinfunction "GND_GND@1") (pintype "bidirectional"))
      (node (ref "USB1") (pin "GND@3") (pinfunction "GND_GND@3") (pintype "bidirectional"))
      (node (ref "X1") (pin "3") (pinfunction "KL_3") (pintype "passive"))
      (node (ref "X3") (pin "1") (pinfunction "KL_1") (pintype "passive"))
    )
    (net (code "8") (name "HEAT") (class "Default")
      (node (ref "U2") (pin "4") (pinfunction "MASS_4") (pintype "passive"))
    )
    (net (code "9") (name "MCO") (class "Default")
      (node (ref "C18") (pin "1") (pinfunction "1_1") (pintype "passive"))
      (node (ref "R21") (pin "2") (pinfunction "2_2") (pintype "passive"))
      (node (ref "TP1") (pin "PP") (pinfunction "TP_PP") (pintype "input"))
    )
    (net (code "10") (name "Net-(C9-Pad1)") (class "Default")
      (node (ref "C9") (pin "1") (pinfunction "1_1") (pintype "passive"))
      (node (ref "R12") (pin "1") (pinfunction "1_1") (pintype "passive"))
    )
    (net (code "11") (name "Net-(C10-Pad1)") (class "Default")
      (node (ref "C10") (pin "1") (pinfunction "1_1") (pintype "passive"))
      (node (ref "R13") (pin "1") (pinfunction "1_1") (pintype "passive"))
    )
    (net (code "12") (name "Net-(D2-C)") (class "Default")
      (node (ref "D2") (pin "3") (pinfunction "C_3") (pintype "passive"))
      (node (ref "R32") (pin "2") (pinfunction "2_2") (pintype "passive"))
    )
    (net (code "13") (name "Net-(F1-1)") (class "Default")
      (node (ref "D1") (pin "2") (pinfunction "2_2") (pintype "passive"))
      (node (ref "F1") (pin "P$1") (pinfunction "1_P$1") (pintype "passive"))
      (node (ref "IC2") (pin "7") (pinfunction "CANH_7") (pintype "bidirectional"))
      (node (ref "R12") (pin "2") (pinfunction "2_2") (pintype "passive"))
    )
    (net (code "14") (name "Net-(F2-1)") (class "Default")
      (node (ref "D1") (pin "1") (pinfunction "1_1") (pintype "passive"))
      (node (ref "F2") (pin "P$1") (pinfunction "1_P$1") (pintype "passive"))
      (node (ref "IC2") (pin "6") (pinfunction "CANL_6") (pintype "bidirectional"))
      (node (ref "R13") (pin "2") (pinfunction "2_2") (pintype "passive"))
    )
    (net (code "15") (name "Net-(IC2-RS)") (class "Default")
      (node (ref "IC2") (pin "8") (pinfunction "RS_8") (pintype "input"))
      (node (ref "R10") (pin "2") (pinfunction "2_2") (pintype "passive"))
      (node (ref "R14") (pin "2") (pinfunction "2_2") (pintype "passive"))
    )
    (net (code "16") (name "Net-(IC2-RXD)") (class "Default")
      (node (ref "IC2") (pin "4") (pinfunction "RXD_4") (pintype "output"))
      (node (ref "R11") (pin "2") (pinfunction "2_2") (pintype "passive"))
    )
    (net (code "17") (name "Net-(IC3-BOOT0)") (class "Default")
      (node (ref "IC3") (pin "44") (pinfunction "BOOT0_44") (pintype "input"))
      (node (ref "R17") (pin "2") (pinfunction "2_2") (pintype "passive"))
    )
    (net (code "18") (name "Net-(IC3-PA8{slash}USART1_CK{slash}MCO{slash}TIM1_CH1)") (class "Default")
      (node (ref "IC3") (pin "29") (pinfunction "PA8/USART1_CK/MCO/TIM1_CH1_29") (pintype "bidirectional"))
      (node (ref "R21") (pin "1") (pinfunction "1_1") (pintype "passive"))
    )
    (net (code "19") (name "Net-(IC3-PC13{slash}TAMPER-RTC)") (class "Default")
      (node (ref "IC3") (pin "2") (pinfunction "PC13/TAMPER-RTC_2") (pintype "bidirectional"))
      (node (ref "R16") (pin "2") (pinfunction "2_2") (pintype "passive"))
    )
    (net (code "20") (name "Net-(IC3-PC14{slash}OSC32_IN)") (class "Default")
      (node (ref "IC3") (pin "3") (pinfunction "PC14/OSC32_IN_3") (pintype "bidirectional"))
      (node (ref "R18") (pin "2") (pinfunction "2_2") (pintype "passive"))
    )
    (net (code "21") (name "Net-(K1A-2)") (class "Default")
      (node (ref "IC4") (pin "16") (pinfunction "16_16") (pintype "open_collector"))
      (node (ref "K1") (pin "A2") (pinfunction "2_A2") (pintype "passive"))
    )
    (net (code "22") (name "Net-(K1B-O)") (class "Default")
      (node (ref "K1") (pin "12") (pinfunction "O_12") (pintype "passive"))
      (node (ref "X2") (pin "3") (pinfunction "KL_3") (pintype "passive"))
    )
    (net (code "23") (name "Net-(K1B-P)") (class "Default")
      (node (ref "K1") (pin "11") (pinfunction "P_11") (pintype "passive"))
      (node (ref "X2") (pin "2") (pinfunction "KL_2") (pintype "passive"))
    )
    (net (code "24") (name "Net-(K1B-S)") (class "Default")
      (node (ref "K1") (pin "14") (pinfunction "S_14") (pintype "passive"))
      (node (ref "X2") (pin "1") (pinfunction "KL_1") (pintype "passive"))
    )
    (net (code "25") (name "Net-(K2A-2)") (class "Default")
      (node (ref "IC4") (pin "15") (pinfunction "15_15") (pintype "open_collector"))
      (node (ref "K2") (pin "A2") (pinfunction "2_A2") (pintype "passive"))
    )
    (net (code "26") (name "Net-(K2B-O)") (class "Default")
      (node (ref "K2") (pin "12") (pinfunction "O_12") (pintype "passive"))
      (node (ref "X2") (pin "6") (pinfunction "KL_6") (pintype "passive"))
    )
    (net (code "27") (name "Net-(K2B-P)") (class "Default")
      (node (ref "K2") (pin "11") (pinfunction "P_11") (pintype "passive"))
      (node (ref "X2") (pin "5") (pinfunction "KL_5") (pintype "passive"))
    )
    (net (code "28") (name "Net-(K2B-S)") (class "Default")
      (node (ref "K2") (pin "14") (pinfunction "S_14") (pintype "passive"))
      (node (ref "X2") (pin "4") (pinfunction "KL_4") (pintype "passive"))
    )
    (net (code "29") (name "Net-(K3A-2)") (class "Default")
      (node (ref "IC4") (pin "14") (pinfunction "14_14") (pintype "open_collector"))
      (node (ref "K3") (pin "A2") (pinfunction "2_A2") (pintype "passive"))
    )
    (net (code "30") (name "Net-(K3B-O)") (class "Default")
      (node (ref "K3") (pin "12") (pinfunction "O_12") (pintype "passive"))
      (node (ref "X2") (pin "9") (pinfunction "KL_9") (pintype "passive"))
    )
    (net (code "31") (name "Net-(K3B-P)") (class "Default")
      (node (ref "K3") (pin "11") (pinfunction "P_11") (pintype "passive"))
      (node (ref "X2") (pin "8") (pinfunction "KL_8") (pintype "passive"))
    )
    (net (code "32") (name "Net-(K3B-S)") (class "Default")
      (node (ref "K3") (pin "14") (pinfunction "S_14") (pintype "passive"))
      (node (ref "X2") (pin "7") (pinfunction "KL_7") (pintype "passive"))
    )
    (net (code "33") (name "Net-(K4A-2)") (class "Default")
      (node (ref "IC4") (pin "13") (pinfunction "13_13") (pintype "open_collector"))
      (node (ref "K4") (pin "A2") (pinfunction "2_A2") (pintype "passive"))
    )
    (net (code "34") (name "Net-(K4B-O)") (class "Default")
      (node (ref "K4") (pin "12") (pinfunction "O_12") (pintype "passive"))
      (node (ref "X2") (pin "12") (pinfunction "KL_12") (pintype "passive"))
    )
    (net (code "35") (name "Net-(K4B-P)") (class "Default")
      (node (ref "K4") (pin "11") (pinfunction "P_11") (pintype "passive"))
      (node (ref "X2") (pin "11") (pinfunction "KL_11") (pintype "passive"))
    )
    (net (code "36") (name "Net-(K4B-S)") (class "Default")
      (node (ref "K4") (pin "14") (pinfunction "S_14") (pintype "passive"))
      (node (ref "X2") (pin "10") (pinfunction "KL_10") (pintype "passive"))
    )
    (net (code "37") (name "Net-(LED1-PadA)") (class "Default")
      (node (ref "LED1") (pin "A") (pinfunction "A_A") (pintype "passive"))
      (node (ref "R15") (pin "2") (pinfunction "2_2") (pintype "passive"))
    )
    (net (code "38") (name "Net-(LED2-PadA)") (class "Default")
      (node (ref "LED2") (pin "A") (pinfunction "A_A") (pintype "passive"))
      (node (ref "R33") (pin "2") (pinfunction "2_2") (pintype "passive"))
    )
    (net (code "39") (name "Net-(LED3-PadA)") (class "Default")
      (node (ref "LED3") (pin "A") (pinfunction "A_A") (pintype "passive"))
      (node (ref "R34") (pin "2") (pinfunction "2_2") (pintype "passive"))
    )
    (net (code "40") (name "Net-(LED4-PadC)") (class "Default")
      (node (ref "LED4") (pin "C") (pinfunction "C_C") (pintype "passive"))
      (node (ref "R35") (pin "2") (pinfunction "2_2") (pintype "passive"))
    )
    (net (code "41") (name "Net-(R26-Pad2)") (class "Default")
      (node (ref "R26") (pin "2") (pinfunction "2_2") (pintype "passive"))
      (node (ref "R28") (pin "1") (pinfunction "1_1") (pintype "passive"))
      (node (ref "USB1") (pin "D+") (pinfunction "D+_D+") (pintype "bidirectional"))
    )
    (net (code "42") (name "Net-(R27-Pad2)") (class "Default")
      (node (ref "R27") (pin "2") (pinfunction "2_2") (pintype "passive"))
      (node (ref "USB1") (pin "D-") (pinfunction "D-_D-") (pintype "bidirectional"))
    )
    (net (code "43") (name "Net-(SW2-S)") (class "Default")
      (node (ref "R2") (pin "1") (pinfunction "1_1") (pintype "passive"))
      (node (ref "R3") (pin "1") (pinfunction "1_1") (pintype "passive"))
      (node (ref "R4") (pin "2") (pinfunction "2_2") (pintype "passive"))
      (node (ref "SW2") (pin "2") (pinfunction "S_2") (pintype "passive"))
    )
    (net (code "44") (name "Net-(X3B-KL)") (class "Default")
      (node (ref "D3") (pin "A") (pinfunction "A_A") (pintype "passive"))
      (node (ref "X3") (pin "2") (pinfunction "KL_2") (pintype "passive"))
    )
    (net (code "45") (name "OSC_IN") (class "Default")
      (node (ref "C2") (pin "1") (pinfunction "1_1") (pintype "passive"))
      (node (ref "IC1") (pin "5") (pinfunction "OSC_IN/(PD0/CANRX)_5") (pintype "input"))
      (node (ref "Q1") (pin "1") (pinfunction "1_1") (pintype "passive"))
      (node (ref "R5") (pin "1") (pinfunction "1_1") (pintype "passive"))
    )
    (net (code "46") (name "OSC_OUT") (class "Default")
      (node (ref "C3") (pin "1") (pinfunction "1_1") (pintype "passive"))
      (node (ref "IC1") (pin "6") (pinfunction "OSC_OUT/(PD1/CANTX)_6") (pintype "output"))
      (node (ref "Q1") (pin "2") (pinfunction "2_2") (pintype "passive"))
      (node (ref "R5") (pin "2") (pinfunction "2_2") (pintype "passive"))
    )
    (net (code "47") (name "PA0") (class "Default")
      (node (ref "IC1") (pin "10") (pinfunction "PA0/WKUP/USART2_CTS/ADC12_IN0/TIM2_CH1_ETR_10") (pintype "bidirectional"))
      (node (ref "J1") (pin "40") (pinfunction "20_40") (pintype "passive"))
    )
    (net (code "48") (name "PA1") (class "Default")
      (node (ref "IC1") (pin "11") (pinfunction "PA1/USART2_RTS/ADC12_IN1/TIM2_CH2_11") (pintype "bidirectional"))
      (node (ref "J1") (pin "39") (pinfunction "19_39") (pintype "passive"))
    )
    (net (code "49") (name "PA2") (class "Default")
      (node (ref "IC1") (pin "12") (pinfunction "PA2/USART2_TX/ADC12_IN2/TIM2_CH3_12") (pintype "bidirectional"))
      (node (ref "J1") (pin "38") (pinfunction "18_38") (pintype "passive"))
    )
    (net (code "50") (name "PA3") (class "Default")
      (node (ref "IC1") (pin "13") (pinfunction "PA3/USART2_RX/ADC12_IN3/TIM2_CH4_13") (pintype "bidirectional"))
      (node (ref "J1") (pin "37") (pinfunction "17_37") (pintype "passive"))
    )
    (net (code "51") (name "PA4") (class "Default")
      (node (ref "IC1") (pin "14") (pinfunction "PA4/SPI1_NSS/ADC12_IN4/USART2_CK_14") (pintype "bidirectional"))
      (node (ref "J1") (pin "36") (pinfunction "16_36") (pintype "passive"))
    )
    (net (code "52") (name "PA5") (class "Default")
      (node (ref "IC1") (pin "15") (pinfunction "PA5/SPI1_SCK/ADC12_IN5_15") (pintype "bidirectional"))
      (node (ref "J1") (pin "35") (pinfunction "15_35") (pintype "passive"))
    )
    (net (code "53") (name "PA6") (class "Default")
      (node (ref "IC1") (pin "16") (pinfunction "PA6/SPI1_MISO/ADC12_IN6/TIM3_CH1_16") (pintype "bidirectional"))
      (node (ref "J1") (pin "34") (pinfunction "14_34") (pintype "passive"))
    )
    (net (code "54") (name "PA7") (class "Default")
      (node (ref "IC1") (pin "17") (pinfunction "PA7SPI1_MOSI/ADC12_IN7/TIM3_CH2_17") (pintype "bidirectional"))
      (node (ref "J1") (pin "33") (pinfunction "13_33") (pintype "passive"))
    )
    (net (code "55") (name "PA8") (class "Default")
      (node (ref "IC1") (pin "29") (pinfunction "PA8/USART1_CK/MCO/TIM1_CH1_29") (pintype "bidirectional"))
      (node (ref "J1") (pin "22") (pinfunction "2_22") (pintype "passive"))
    )
    (net (code "56") (name "PA9{slash}TXD1") (class "Default")
      (node (ref "IC1") (pin "30") (pinfunction "PA9/USART1_TX/TIM1_CH2_30") (pintype "bidirectional"))
      (node (ref "J1") (pin "23") (pinfunction "3_23") (pintype "passive"))
    )
    (net (code "57") (name "PA10{slash}RXD1") (class "Default")
      (node (ref "IC1") (pin "31") (pinfunction "PA10/USART1_RX/TIM1_CH3_31") (pintype "bidirectional"))
      (node (ref "J1") (pin "24") (pinfunction "4_24") (pintype "passive"))
    )
    (net (code "58") (name "PA11{slash}USBDM") (class "Default")
      (node (ref "IC1") (pin "32") (pinfunction "PA11/CANRX/USBDM/USART1_CTS/TIM1_CH4_32") (pintype "bidirectional"))
      (node (ref "J1") (pin "25") (pinfunction "5_25") (pintype "passive"))
    )
    (net (code "59") (name "PA12{slash}USBDP") (class "Default")
      (node (ref "IC1") (pin "33") (pinfunction "PA12/CANTX/USBDP/USART1_RTS/TIM1_ETR_33") (pintype "bidirectional"))
      (node (ref "J1") (pin "26") (pinfunction "6_26") (pintype "passive"))
    )
    (net (code "60") (name "PA13{slash}SWDIO") (class "Default")
      (node (ref "IC1") (pin "34") (pinfunction "JTMS-SWDIO/(PA13)_34") (pintype "bidirectional"))
      (node (ref "J1") (pin "27") (pinfunction "7_27") (pintype "passive"))
      (node (ref "R8") (pin "1") (pinfunction "1_1") (pintype "passive"))
    )
    (net (code "61") (name "PA14{slash}SWCLK") (class "Default")
      (node (ref "IC1") (pin "37") (pinfunction "JTCK-SWCLK/(PA14)_37") (pintype "bidirectional"))
      (node (ref "J1") (pin "28") (pinfunction "8_28") (pintype "passive"))
      (node (ref "R7") (pin "1") (pinfunction "1_1") (pintype "passive"))
    )
    (net (code "62") (name "PA15") (class "Default")
      (node (ref "IC1") (pin "38") (pinfunction "JTDI/(TIM2_CH1_ETR/PA15/SPI1_NSS)_38") (pintype "bidirectional"))
      (node (ref "J1") (pin "29") (pinfunction "9_29") (pintype "passive"))
    )
    (net (code "63") (name "PB0") (class "Default")
      (node (ref "IC1") (pin "18") (pinfunction "PB0/ADC12_IN8/TIM3_CH3/(TIM1_CH2N)_18") (pintype "bidirectional"))
      (node (ref "J1") (pin "1") (pinfunction "1_1") (pintype "passive"))
    )
    (net (code "64") (name "PB1") (class "Default")
      (node (ref "IC1") (pin "19") (pinfunction "PB1/ADC12_IN9/TIM3_CH4/(TIM1_CH3N)_19") (pintype "bidirectional"))
      (node (ref "J1") (pin "2") (pinfunction "2_2") (pintype "passive"))
    )
    (net (code "65") (name "PB2") (class "Default")
      (node (ref "IC1") (pin "20") (pinfunction "PB2/BOOT1_20") (pintype "bidirectional"))
      (node (ref "J1") (pin "3") (pinfunction "3_3") (pintype "passive"))
      (node (ref "R15") (pin "1") (pinfunction "1_1") (pintype "passive"))
      (node (ref "R6") (pin "1") (pinfunction "1_1") (pintype "passive"))
    )
    (net (code "66") (name "PB3{slash}SWO") (class "Default")
      (node (ref "IC1") (pin "39") (pinfunction "JTDO/(TIM2_CH2/PB3/TRACESWO/SPI1_SCK)_39") (pintype "bidirectional"))
      (node (ref "J1") (pin "4") (pinfunction "4_4") (pintype "passive"))
      (node (ref "R9") (pin "1") (pinfunction "1_1") (pintype "passive"))
    )
    (net (code "67") (name "PB4") (class "Default")
      (node (ref "IC1") (pin "40") (pinfunction "JTNRST/(PB4/TIM3_CH1/SPI1_MISO)_40") (pintype "bidirectional"))
      (node (ref "J1") (pin "5") (pinfunction "5_5") (pintype "passive"))
    )
    (net (code "68") (name "PB5") (class "Default")
      (node (ref "IC1") (pin "41") (pinfunction "PB5/I2C1_SMBA/(TIM3_CH2/SPI1_MOSI)_41") (pintype "bidirectional"))
      (node (ref "J1") (pin "6") (pinfunction "6_6") (pintype "passive"))
    )
    (net (code "69") (name "PB6{slash}SCL1") (class "Default")
      (node (ref "IC1") (pin "42") (pinfunction "PB6/I2C1_SCL/TIM4_CH1/(USART1_TX)_42") (pintype "bidirectional"))
      (node (ref "J1") (pin "7") (pinfunction "7_7") (pintype "passive"))
    )
    (net (code "70") (name "PB7{slash}SDA1") (class "Default")
      (node (ref "IC1") (pin "43") (pinfunction "PB7/I2C1_SDA/TIM4_CH2/(USART1_RX)_43") (pintype "bidirectional"))
      (node (ref "J1") (pin "8") (pinfunction "8_8") (pintype "passive"))
    )
    (net (code "71") (name "PB8{slash}CANRX") (class "Default")
      (node (ref "IC1") (pin "45") (pinfunction "PB8/TIM4_CH3/(I2C1_SCL/CANRX)_45") (pintype "bidirectional"))
      (node (ref "J1") (pin "14") (pinfunction "14_14") (pintype "passive"))
      (node (ref "R11") (pin "1") (pinfunction "1_1") (pintype "passive"))
    )
    (net (code "72") (name "PB9{slash}CANTX") (class "Default")
      (node (ref "IC1") (pin "46") (pinfunction "PB9/TIM4_CH4/(I2C1_SDA/CANTX)_46") (pintype "bidirectional"))
      (node (ref "IC2") (pin "1") (pinfunction "TXD_1") (pintype "input"))
      (node (ref "J1") (pin "15") (pinfunction "15_15") (pintype "passive"))
    )
    (net (code "73") (name "PB10") (class "Default")
      (node (ref "IC1") (pin "21") (pinfunction "PB10/I2C2_SCL/USART3_TX/(TIM2_CH3)_21") (pintype "bidirectional"))
      (node (ref "J1") (pin "16") (pinfunction "16_16") (pintype "passive"))
    )
    (net (code "74") (name "PB11") (class "Default")
      (node (ref "IC1") (pin "22") (pinfunction "PB11/I2C2_SDA/USART3_RX/(TIM2_CH4)_22") (pintype "bidirectional"))
      (node (ref "J1") (pin "17") (pinfunction "17_17") (pintype "passive"))
    )
    (net (code "75") (name "PB12") (class "Default")
      (node (ref "IC1") (pin "25") (pinfunction "PB12/SPI2_NSS/I2C2_SMBAI/TIM1_BKIN/USART3_CK_25") (pintype "bidirectional"))
      (node (ref "J1") (pin "18") (pinfunction "18_18") (pintype "passive"))
    )
    (net (code "76") (name "PB13") (class "Default")
      (node (ref "IC1") (pin "26") (pinfunction "PB13/SPI2_SCK/TIM1_CH1N/USART3_CTS_26") (pintype "bidirectional"))
      (node (ref "J1") (pin "19") (pinfunction "19_19") (pintype "passive"))
    )
    (net (code "77") (name "PB14") (class "Default")
      (node (ref "IC1") (pin "27") (pinfunction "PB14/SPI2_MISO/TIM1_CH2N/USART3_RTS_27") (pintype "bidirectional"))
      (node (ref "J1") (pin "20") (pinfunction "20_20") (pintype "passive"))
    )
    (net (code "78") (name "PB15") (class "Default")
      (node (ref "IC1") (pin "28") (pinfunction "PB15/SPI2_MOSI/TIM1_CH3N_28") (pintype "bidirectional"))
      (node (ref "J1") (pin "21") (pinfunction "1_21") (pintype "passive"))
    )
    (net (code "79") (name "PC13") (class "Default")
      (node (ref "IC1") (pin "2") (pinfunction "PC13/TAMPER-RTC_2") (pintype "bidirectional"))
      (node (ref "R3") (pin "2") (pinfunction "2_2") (pintype "passive"))
    )
    (net (code "80") (name "PC14{slash}OSC32_IN") (class "Default")
      (node (ref "IC1") (pin "3") (pinfunction "PC14/OSC32_IN_3") (pintype "bidirectional"))
      (node (ref "J1") (pin "13") (pinfunction "13_13") (pintype "passive"))
    )
    (net (code "81") (name "PC15{slash}OSC32_OUT") (class "Default")
      (node (ref "IC1") (pin "4") (pinfunction "PC15/OSC32_OUT_4") (pintype "bidirectional"))
      (node (ref "J1") (pin "12") (pinfunction "12_12") (pintype "passive"))
    )
    (net (code "82") (name "S2.3V3") (class "Default")
      (node (ref "3V3") (pin "1") (pinfunction "1_1") (pintype "passive"))
      (node (ref "C26") (pin "1") (pinfunction "1_1") (pintype "passive"))
      (node (ref "C28") (pin "+") (pinfunction "+_+") (pintype "passive"))
      (node (ref "MOD1") (pin "10") (pinfunction "+3V3_10") (pintype "power_in"))
      (node (ref "U2") (pin "2") (pinfunction "OUT_2") (pintype "power_in"))
    )
    (net (code "83") (name "S2.AVCC") (class "Default")
      (node (ref "AVCC") (pin "1") (pinfunction "1_1") (pintype "passive"))
      (node (ref "MOD1") (pin "30") (pinfunction "AVCC_30") (pintype "power_in"))
    )
    (net (code "84") (name "S2.IN1") (class "Default")
      (node (ref "IC4") (pin "1") (pinfunction "1_1") (pintype "input"))
      (node (ref "IN1") (pin "1") (pinfunction "1_1") (pintype "passive"))
    )
    (net (code "85") (name "S2.IN2") (class "Default")
      (node (ref "IC4") (pin "2") (pinfunction "2_2") (pintype "input"))
      (node (ref "IN2") (pin "1") (pinfunction "1_1") (pintype "passive"))
    )
    (net (code "86") (name "S2.IN3") (class "Default")
      (node (ref "IC4") (pin "3") (pinfunction "3_3") (pintype "input"))
      (node (ref "IN3") (pin "1") (pinfunction "1_1") (pintype "passive"))
    )
    (net (code "87") (name "S2.IN4") (class "Default")
      (node (ref "IC4") (pin "4") (pinfunction "4_4") (pintype "input"))
      (node (ref "IN4") (pin "1") (pinfunction "1_1") (pintype "passive"))
    )
    (net (code "88") (name "S2.IN5") (class "Default")
      (node (ref "IC4") (pin "5") (pinfunction "5_5") (pintype "input"))
      (node (ref "IN5") (pin "1") (pinfunction "1_1") (pintype "passive"))
    )
    (net (code "89") (name "S2.IN6") (class "Default")
      (node (ref "IC4") (pin "6") (pinfunction "6_6") (pintype "input"))
      (node (ref "IN6") (pin "1") (pinfunction "1_1") (pintype "passive"))
    )
    (net (code "90") (name "S2.IN7") (class "Default")
      (node (ref "IC4") (pin "7") (pinfunction "7_7") (pintype "input"))
      (node (ref "IN7") (pin "1") (pinfunction "1_1") (pintype "passive"))
    )
    (net (code "91") (name "S2.OSC32_IN") (class "Default")
      (node (ref "C24") (pin "1") (pinfunction "1_1") (pintype "passive"))
      (node (ref "MOD1") (pin "13") (pinfunction "PC14_13") (pintype "bidirectional"))
      (node (ref "PC14") (pin "1") (pinfunction "1_1") (pintype "passive"))
      (node (ref "Q3") (pin "2") (pinfunction "2_2") (pintype "passive"))
      (node (ref "R36") (pin "2") (pinfunction "2_2") (pintype "passive"))
    )
    (net (code "92") (name "S2.OSC32_OUT") (class "Default")
      (node (ref "C23") (pin "1") (pinfunction "1_1") (pintype "passive"))
      (node (ref "MOD1") (pin "12") (pinfunction "PC15_12") (pintype "bidirectional"))
      (node (ref "PC15") (pin "1") (pinfunction "1_1") (pintype "passive"))
      (node (ref "Q3") (pin "1") (pinfunction "1_1") (pintype "passive"))
      (node (ref "R36") (pin "1") (pinfunction "1_1") (pintype "passive"))
    )
    (net (code "93") (name "S2.OUT5") (class "Default")
      (node (ref "IC4") (pin "12") (pinfunction "12_12") (pintype "open_collector"))
      (node (ref "OUT5") (pin "1") (pinfunction "1_1") (pintype "passive"))
    )
    (net (code "94") (name "S2.OUT6") (class "Default")
      (node (ref "IC4") (pin "11") (pinfunction "11_11") (pintype "open_collector"))
      (node (ref "OUT6") (pin "1") (pinfunction "1_1") (pintype "passive"))
    )
    (net (code "95") (name "S2.OUT7") (class "Default")
      (node (ref "IC4") (pin "10") (pinfunction "10_10") (pintype "open_collector"))
      (node (ref "OUT7") (pin "1") (pinfunction "1_1") (pintype "passive"))
    )
    (net (code "96") (name "S2.PA0") (class "Default")
      (node (ref "MOD1") (pin "40") (pinfunction "PA0_40") (pintype "bidirectional"))
      (node (ref "PA0") (pin "1") (pinfunction "1_1") (pintype "passive"))
    )
    (net (code "97") (name "S2.PA1") (class "Default")
      (node (ref "MOD1") (pin "39") (pinfunction "PA1_39") (pintype "bidirectional"))
      (node (ref "PA1") (pin "1") (pinfunction "1_1") (pintype "passive"))
    )
    (net (code "98") (name "S2.PA2") (class "Default")
      (node (ref "MOD1") (pin "38") (pinfunction "PA2_38") (pintype "bidirectional"))
      (node (ref "PA2") (pin "1") (pinfunction "1_1") (pintype "passive"))
    )
    (net (code "99") (name "S2.PA3") (class "Default")
      (node (ref "MOD1") (pin "37") (pinfunction "PA3_37") (pintype "bidirectional"))
      (node (ref "PA3") (pin "1") (pinfunction "1_1") (pintype "passive"))
    )
    (net (code "100") (name "S2.PA4") (class "Default")
      (node (ref "MOD1") (pin "36") (pinfunction "PA4_36") (pintype "bidirectional"))
      (node (ref "PA4") (pin "1") (pinfunction "1_1") (pintype "passive"))
    )
    (net (code "101") (name "S2.PA5") (class "Default")
      (node (ref "MOD1") (pin "35") (pinfunction "PA5_35") (pintype "bidirectional"))
      (node (ref "PA5") (pin "1") (pinfunction "1_1") (pintype "passive"))
    )
    (net (code "102") (name "S2.PA6") (class "Default")
      (node (ref "MOD1") (pin "34") (pinfunction "PA6_34") (pintype "bidirectional"))
      (node (ref "PA6") (pin "1") (pinfunction "1_1") (pintype "passive"))
    )
    (net (code "103") (name "S2.PA7") (class "Default")
      (node (ref "MOD1") (pin "33") (pinfunction "PA7_33") (pintype "bidirectional"))
      (node (ref "PA7") (pin "1") (pinfunction "1_1") (pintype "passive"))
    )
    (net (code "104") (name "S2.PA8") (class "Default")
      (node (ref "MOD1") (pin "22") (pinfunction "PA8_22") (pintype "bidirectional"))
      (node (ref "PA8") (pin "1") (pinfunction "1_1") (pintype "passive"))
    )
    (net (code "105") (name "S2.PA9") (class "Default")
      (node (ref "MOD1") (pin "23") (pinfunction "PA9_23") (pintype "bidirectional"))
      (node (ref "PA9") (pin "1") (pinfunction "1_1") (pintype "passive"))
    )
    (net (code "106") (name "S2.PA10") (class "Default")
      (node (ref "MOD1") (pin "24") (pinfunction "PA10_24") (pintype "bidirectional"))
      (node (ref "PA10") (pin "1") (pinfunction "1_1") (pintype "passive"))
    )
    (net (code "107") (name "S2.PA11") (class "Default")
      (node (ref "MOD1") (pin "25") (pinfunction "PA11_25") (pintype "bidirectional"))
      (node (ref "PA11") (pin "1") (pinfunction "1_1") (pintype "passive"))
    )
    (net (code "108") (name "S2.PA12") (class "Default")
      (node (ref "MOD1") (pin "26") (pinfunction "PA12_26") (pintype "bidirectional"))
      (node (ref "PA12") (pin "1") (pinfunction "1_1") (pintype "passive"))
    )
    (net (code "109") (name "S2.PA13") (class "Default")
      (node (ref "MOD1") (pin "27") (pinfunction "PA13_27") (pintype "bidirectional"))
      (node (ref "PA13") (pin "1") (pinfunction "1_1") (pintype "passive"))
    )
    (net (code "110") (name "S2.PA14") (class "Default")
      (node (ref "MOD1") (pin "28") (pinfunction "PA14_28") (pintype "bidirectional"))
      (node (ref "PA14") (pin "1") (pinfunction "1_1") (pintype "passive"))
    )
    (net (code "111") (name "S2.PA15") (class "Default")
      (node (ref "MOD1") (pin "29") (pinfunction "PA15_29") (pintype "bidirectional"))
      (node (ref "PA15") (pin "1") (pinfunction "1_1") (pintype "passive"))
    )
    (net (code "112") (name "S2.PB0") (class "Default")
      (node (ref "MOD1") (pin "1") (pinfunction "PB0_1") (pintype "bidirectional"))
      (node (ref "PB0") (pin "1") (pinfunction "1_1") (pintype "passive"))
    )
    (net (code "113") (name "S2.PB1") (class "Default")
      (node (ref "MOD1") (pin "2") (pinfunction "PB1_2") (pintype "bidirectional"))
      (node (ref "PB1") (pin "1") (pinfunction "1_1") (pintype "passive"))
    )
    (net (code "114") (name "S2.PB2") (class "Default")
      (node (ref "MOD1") (pin "3") (pinfunction "PB2_3") (pintype "bidirectional"))
      (node (ref "PB2") (pin "1") (pinfunction "1_1") (pintype "passive"))
    )
    (net (code "115") (name "S2.PB3") (class "Default")
      (node (ref "MOD1") (pin "4") (pinfunction "PB3_4") (pintype "bidirectional"))
      (node (ref "PB3") (pin "1") (pinfunction "1_1") (pintype "passive"))
    )
    (net (code "116") (name "S2.PB4") (class "Default")
      (node (ref "MOD1") (pin "5") (pinfunction "PB4_5") (pintype "bidirectional"))
      (node (ref "PB4") (pin "1") (pinfunction "1_1") (pintype "passive"))
    )
    (net (code "117") (name "S2.PB5") (class "Default")
      (node (ref "MOD1") (pin "6") (pinfunction "PB5_6") (pintype "bidirectional"))
      (node (ref "PB5") (pin "1") (pinfunction "1_1") (pintype "passive"))
    )
    (net (code "118") (name "S2.PB6") (class "Default")
      (node (ref "MOD1") (pin "7") (pinfunction "PB6_7") (pintype "bidirectional"))
      (node (ref "PB6") (pin "1") (pinfunction "1_1") (pintype "passive"))
    )
    (net (code "119") (name "S2.PB7") (class "Default")
      (node (ref "MOD1") (pin "8") (pinfunction "PB7_8") (pintype "bidirectional"))
      (node (ref "PB7") (pin "1") (pinfunction "1_1") (pintype "passive"))
    )
    (net (code "120") (name "S2.PB8") (class "Default")
      (node (ref "MOD1") (pin "14") (pinfunction "PB8_14") (pintype "bidirectional"))
      (node (ref "PB8") (pin "1") (pinfunction "1_1") (pintype "passive"))
    )
    (net (code "121") (name "S2.PB9") (class "Default")
      (node (ref "MOD1") (pin "15") (pinfunction "PB9_15") (pintype "bidirectional"))
      (node (ref "PB9") (pin "1") (pinfunction "1_1") (pintype "passive"))
    )
    (net (code "122") (name "S2.PB10") (class "Default")
      (node (ref "MOD1") (pin "16") (pinfunction "PB10_16") (pintype "bidirectional"))
      (node (ref "PB10") (pin "1") (pinfunction "1_1") (pintype "passive"))
    )
    (net (code "123") (name "S2.PB11") (class "Default")
      (node (ref "MOD1") (pin "17") (pinfunction "PB11_17") (pintype "bidirectional"))
      (node (ref "PB11") (pin "1") (pinfunction "1_1") (pintype "passive"))
    )
    (net (code "124") (name "S2.PB12") (class "Default")
      (node (ref "MOD1") (pin "18") (pinfunction "PB12_18") (pintype "bidirectional"))
      (node (ref "PB12") (pin "1") (pinfunction "1_1") (pintype "passive"))
    )
    (net (code "125") (name "S2.PB13") (class "Default")
      (node (ref "MOD1") (pin "19") (pinfunction "PB13_19") (pintype "bidirectional"))
      (node (ref "PB13") (pin "1") (pinfunction "1_1") (pintype "passive"))
    )
    (net (code "126") (name "S2.PB14") (class "Default")
      (node (ref "MOD1") (pin "20") (pinfunction "PB14_20") (pintype "bidirectional"))
      (node (ref "PB14") (pin "1") (pinfunction "1_1") (pintype "passive"))
    )
    (net (code "127") (name "S2.PB15") (class "Default")
      (node (ref "MOD1") (pin "21") (pinfunction "PB15_21") (pintype "bidirectional"))
      (node (ref "PB15") (pin "1") (pinfunction "1_1") (pintype "passive"))
    )
    (net (code "128") (name "S2.VBAT") (class "Default")
      (node (ref "G1") (pin "+") (pinfunction "+_+") (pintype "passive"))
      (node (ref "MOD1") (pin "32") (pinfunction "VBAT_32") (pintype "power_in"))
      (node (ref "VBAT") (pin "1") (pinfunction "1_1") (pintype "passive"))
    )
    (net (code "129") (name "S3.AIN1") (class "Default")
      (node (ref "IC3") (pin "10") (pinfunction "PA0/WKUP/USART2_CTS/ADC12_IN0/TIM2_CH1_ETR_10") (pintype "bidirectional"))
      (node (ref "R29") (pin "1") (pinfunction "1_1") (pintype "passive"))
      (node (ref "R30") (pin "2") (pinfunction "2_2") (pintype "passive"))
      (node (ref "R32") (pin "1") (pinfunction "1_1") (pintype "passive"))
    )
    (net (code "130") (name "S3.LED") (class "Default")
      (node (ref "IC3") (pin "30") (pinfunction "PA9/USART1_TX/TIM1_CH2_30") (pintype "bidirectional"))
      (node (ref "R34") (pin "1") (pinfunction "1_1") (pintype "passive"))
      (node (ref "R35") (pin "1") (pinfunction "1_1") (pintype "passive"))
    )
    (net (code "131") (name "S3.OSC_IN") (class "Default")
      (node (ref "C11") (pin "1") (pinfunction "1_1") (pintype "passive"))
      (node (ref "IC3") (pin "5") (pinfunction "OSC_IN/(PD0/CANRX)_5") (pintype "input"))
      (node (ref "Q2") (pin "1") (pinfunction "1_1") (pintype "passive"))
    )
    (net (code "132") (name "S3.OSC_OUT") (class "Default")
      (node (ref "C12") (pin "1") (pinfunction "1_1") (pintype "passive"))
      (node (ref "IC3") (pin "6") (pinfunction "OSC_OUT/(PD1/CANTX)_6") (pintype "output"))
      (node (ref "Q2") (pin "2") (pinfunction "2_2") (pintype "passive"))
    )
    (net (code "133") (name "S3.SWCLK") (class "Default")
      (node (ref "IC3") (pin "37") (pinfunction "JTCK-SWCLK/(PA14)_37") (pintype "bidirectional"))
      (node (ref "JP1") (pin "2") (pinfunction "2_2") (pintype "passive"))
    )
    (net (code "134") (name "S3.SWDIO") (class "Default")
      (node (ref "IC3") (pin "34") (pinfunction "JTMS-SWDIO/(PA13)_34") (pintype "bidirectional"))
      (node (ref "JP1") (pin "4") (pinfunction "4_4") (pintype "passive"))
    )
    (net (code "135") (name "S3.SWIM") (class "Default")
      (node (ref "IC3") (pin "22") (pinfunction "PB11/I2C2_SDA/USART3_RX/(TIM2_CH4)_22") (pintype "bidirectional"))
      (node (ref "IC3") (pin "45") (pinfunction "PB8/TIM4_CH3/(I2C1_SCL/CANRX)_45") (pintype "bidirectional"))
    )
    (net (code "136") (name "S3.SWIM_IN") (class "Default")
      (node (ref "IC3") (pin "21") (pinfunction "PB10/I2C2_SCL/USART3_TX/(TIM2_CH3)_21") (pintype "bidirectional"))
      (node (ref "IC3") (pin "43") (pinfunction "PB7/I2C1_SDA/TIM4_CH2/(USART1_RX)_43") (pintype "bidirectional"))
      (node (ref "IC3") (pin "46") (pinfunction "PB9/TIM4_CH4/(I2C1_SDA/CANTX)_46") (pintype "bidirectional"))
    )
    (net (code "137") (name "S3.SWIM_RST") (class "Default")
      (node (ref "IC3") (pin "42") (pinfunction "PB6/I2C1_SCL/TIM4_CH1/(USART1_TX)_42") (pintype "bidirectional"))
    )
    (net (code "138") (name "S3.SWIM_RST_IN") (class "Default")
      (node (ref "IC3") (pin "41") (pinfunction "PB5/I2C1_SMBA/(TIM3_CH2/SPI1_MOSI)_41") (pintype "bidirectional"))
    )
    (net (code "139") (name "S3.T_JTCK") (class "Default")
      (node (ref "IC3") (pin "15") (pinfunction "PA5/SPI1_SCK/ADC12_IN5_15") (pintype "bidirectional"))
      (node (ref "IC3") (pin "26") (pinfunction "PB13/SPI2_SCK/TIM1_CH1N/USART3_CTS_26") (pintype "bidirectional"))
      (node (ref "R22") (pin "1") (pinfunction "1_1") (pintype "passive"))
    )
    (net (code "140") (name "S3.T_JTDI") (class "Default")
      (node (ref "IC3") (pin "17") (pinfunction "PA7SPI1_MOSI/ADC12_IN7/TIM3_CH2_17") (pintype "bidirectional"))
    )
    (net (code "141") (name "S3.T_JTDO") (class "Default")
      (node (ref "IC3") (pin "16") (pinfunction "PA6/SPI1_MISO/ADC12_IN6/TIM3_CH1_16") (pintype "bidirectional"))
    )
    (net (code "142") (name "S3.T_JTMS") (class "Default")
      (node (ref "IC3") (pin "27") (pinfunction "PB14/SPI2_MISO/TIM1_CH2N/USART3_RTS_27") (pintype "bidirectional"))
      (node (ref "R19") (pin "2") (pinfunction "2_2") (pintype "passive"))
      (node (ref "R23") (pin "1") (pinfunction "1_1") (pintype "passive"))
    )
    (net (code "143") (name "S3.T_NRST") (class "Default")
      (node (ref "IC3") (pin "18") (pinfunction "PB0/ADC12_IN8/TIM3_CH3/(TIM1_CH2N)_18") (pintype "bidirectional"))
      (node (ref "R25") (pin "1") (pinfunction "1_1") (pintype "passive"))
    )
    (net (code "144") (name "S3.T_SWDIO_IN") (class "Default")
      (node (ref "IC3") (pin "25") (pinfunction "PB12/SPI2_NSS/I2C2_SMBAI/TIM1_BKIN/USART3_CK_25") (pintype "bidirectional"))
      (node (ref "R19") (pin "1") (pinfunction "1_1") (pintype "passive"))
    )
    (net (code "145") (name "S3.T_SWO") (class "Default")
      (node (ref "IC3") (pin "31") (pinfunction "PA10/USART1_RX/TIM1_CH3_31") (pintype "bidirectional"))
      (node (ref "R24") (pin "1") (pinfunction "1_1") (pintype "passive"))
    )
    (net (code "146") (name "S3.USBDM") (class "Default")
      (node (ref "IC3") (pin "32") (pinfunction "PA11/CANRX/USBDM/USART1_CTS/TIM1_CH4_32") (pintype "bidirectional"))
      (node (ref "R27") (pin "1") (pinfunction "1_1") (pintype "passive"))
    )
    (net (code "147") (name "S3.USBDP") (class "Default")
      (node (ref "IC3") (pin "33") (pinfunction "PA12/CANTX/USBDP/USART1_RTS/TIM1_ETR_33") (pintype "bidirectional"))
      (node (ref "R26") (pin "1") (pinfunction "1_1") (pintype "passive"))
    )
    (net (code "148") (name "SWCLK") (class "Default")
      (node (ref "R22") (pin "2") (pinfunction "2_2") (pintype "passive"))
      (node (ref "R7") (pin "2") (pinfunction "2_2") (pintype "passive"))
      (node (ref "SWD1") (pin "2") (pinfunction "2_2") (pintype "passive"))
      (node (ref "SWD2") (pin "2") (pinfunction "2_2") (pintype "passive"))
    )
    (net (code "149") (name "SWDIO") (class "Default")
      (node (ref "R23") (pin "2") (pinfunction "2_2") (pintype "passive"))
      (node (ref "R8") (pin "2") (pinfunction "2_2") (pintype "passive"))
      (node (ref "SWD1") (pin "4") (pinfunction "4_4") (pintype "passive"))
      (node (ref "SWD2") (pin "4") (pinfunction "4_4") (pintype "passive"))
    )
    (net (code "150") (name "SWO") (class "Default")
      (node (ref "R24") (pin "2") (pinfunction "2_2") (pintype "passive"))
      (node (ref "R9") (pin "2") (pinfunction "2_2") (pintype "passive"))
      (node (ref "SWD1") (pin "6") (pinfunction "6_6") (pintype "passive"))
      (node (ref "SWD2") (pin "6") (pinfunction "6_6") (pintype "passive"))
    )
    (net (code "151") (name "VBAT") (class "Default")
      (node (ref "IC1") (pin "1") (pinfunction "VBAT_1") (pintype "power_in"))
      (node (ref "J1") (pin "32") (pinfunction "12_32") (pintype "passive"))
    )
    (net (code "152") (name "VCC") (class "Default")
      (node (ref "C13") (pin "1") (pinfunction "1_1") (pintype "passive"))
      (node (ref "C14") (pin "1") (pinfunction "1_1") (pintype "passive"))
      (node (ref "C15") (pin "1") (pinfunction "1_1") (pintype "passive"))
      (node (ref "C16") (pin "1") (pinfunction "1_1") (pintype "passive"))
      (node (ref "C20") (pin "1") (pinfunction "1_1") (pintype "passive"))
      (node (ref "C21") (pin "+") (pinfunction "+_+") (pintype "passive"))
      (node (ref "IC3") (pin "1") (pinfunction "VBAT_1") (pintype "power_in"))
      (node (ref "IC3") (pin "24") (pinfunction "VDD_24") (pintype "power_in"))
      (node (ref "IC3") (pin "36") (pinfunction "VDD_36") (pintype "power_in"))
      (node (ref "IC3") (pin "48") (pinfunction "VDD_48") (pintype "power_in"))
      (node (ref "IC3") (pin "9") (pinfunction "VDDA_9") (pintype "power_in"))
      (node (ref "JP1") (pin "1") (pinfunction "1_1") (pintype "passive"))
      (node (ref "LED4") (pin "A") (pinfunction "A_A") (pintype "passive"))
      (node (ref "R20") (pin "2") (pinfunction "2_2") (pintype "passive"))
      (node (ref "R28") (pin "2") (pinfunction "2_2") (pintype "passive"))
      (node (ref "R29") (pin "2") (pinfunction "2_2") (pintype "passive"))
      (node (ref "R33") (pin "1") (pinfunction "1_1") (pintype "passive"))
      (node (ref "U1") (pin "2") (pinfunction "OUT_2") (pintype "power_in"))
    )
    (net (code "153") (name "unconnected-(IC2-VREF-Pad5)") (class "Default")
      (node (ref "IC2") (pin "5") (pinfunction "VREF_5") (pintype "passive"))
    )
    (net (code "154") (name "unconnected-(IC3-JTDI{slash}(TIM2_CH1_ETR{slash}PA15{slash}SPI1_NSS)-Pad38)") (class "Default")
      (node (ref "IC3") (pin "38") (pinfunction "JTDI/(TIM2_CH1_ETR/PA15/SPI1_NSS)_38") (pintype "bidirectional"))
    )
    (net (code "155") (name "unconnected-(IC3-JTDO{slash}(TIM2_CH2{slash}PB3{slash}TRACESWO{slash}SPI1_SCK)-Pad39)") (class "Default")
      (node (ref "IC3") (pin "39") (pinfunction "JTDO/(TIM2_CH2/PB3/TRACESWO/SPI1_SCK)_39") (pintype "bidirectional"))
    )
    (net (code "156") (name "unconnected-(IC3-JTNRST{slash}(PB4{slash}TIM3_CH1{slash}SPI1_MISO)-Pad40)") (class "Default")
      (node (ref "IC3") (pin "40") (pinfunction "JTNRST/(PB4/TIM3_CH1/SPI1_MISO)_40") (pintype "bidirectional"))
    )
    (net (code "157") (name "unconnected-(IC3-PA1{slash}USART2_RTS{slash}ADC12_IN1{slash}TIM2_CH2-Pad11)") (class "Default")
      (node (ref "IC3") (pin "11") (pinfunction "PA1/USART2_RTS/ADC12_IN1/TIM2_CH2_11") (pintype "bidirectional"))
    )
    (net (code "158") (name "unconnected-(IC3-PA2{slash}USART2_TX{slash}ADC12_IN2{slash}TIM2_CH3-Pad12)") (class "Default")
      (node (ref "IC3") (pin "12") (pinfunction "PA2/USART2_TX/ADC12_IN2/TIM2_CH3_12") (pintype "bidirectional"))
    )
    (net (code "159") (name "unconnected-(IC3-PA3{slash}USART2_RX{slash}ADC12_IN3{slash}TIM2_CH4-Pad13)") (class "Default")
      (node (ref "IC3") (pin "13") (pinfunction "PA3/USART2_RX/ADC12_IN3/TIM2_CH4_13") (pintype "bidirectional"))
    )
    (net (code "160") (name "unconnected-(IC3-PA4{slash}SPI1_NSS{slash}ADC12_IN4{slash}USART2_CK-Pad14)") (class "Default")
      (node (ref "IC3") (pin "14") (pinfunction "PA4/SPI1_NSS/ADC12_IN4/USART2_CK_14") (pintype "bidirectional"))
    )
    (net (code "161") (name "unconnected-(IC3-PB1{slash}ADC12_IN9{slash}TIM3_CH4{slash}(TIM1_CH3N)-Pad19)") (class "Default")
      (node (ref "IC3") (pin "19") (pinfunction "PB1/ADC12_IN9/TIM3_CH4/(TIM1_CH3N)_19") (pintype "bidirectional"))
    )
    (net (code "162") (name "unconnected-(IC3-PB15{slash}SPI2_MOSI{slash}TIM1_CH3N-Pad28)") (class "Default")
      (node (ref "IC3") (pin "28") (pinfunction "PB15/SPI2_MOSI/TIM1_CH3N_28") (pintype "bidirectional"))
    )
    (net (code "163") (name "unconnected-(IC3-PC15{slash}OSC32_OUT-Pad4)") (class "Default")
      (node (ref "IC3") (pin "4") (pinfunction "PC15/OSC32_OUT_4") (pintype "bidirectional"))
    )
    (net (code "164") (name "unconnected-(U1-MASS-Pad4)") (class "Default")
      (node (ref "U1") (pin "4") (pinfunction "MASS_4") (pintype "passive"))
    )
    (net (code "165") (name "~{RESET}") (class "Default")
      (node (ref "C1") (pin "1") (pinfunction "1_1") (pintype "passive"))
      (node (ref "IC1") (pin "7") (pinfunction "~{RESET}_7") (pintype "input"))
      (node (ref "J1") (pin "9") (pinfunction "9_9") (pintype "passive"))
      (node (ref "R1") (pin "1") (pinfunction "1_1") (pintype "passive"))
      (node (ref "R25") (pin "2") (pinfunction "2_2") (pintype "passive"))
      (node (ref "SW1") (pin "2") (pinfunction "S_2") (pintype "passive"))
      (node (ref "SWD1") (pin "5") (pinfunction "5_5") (pintype "passive"))
      (node (ref "SWD2") (pin "5") (pinfunction "5_5") (pintype "passive"))
    )
    (net (code "166") (name "~{S2.RESET}") (class "Default")
      (node (ref "MOD1") (pin "9") (pinfunction "~{RESET}_9") (pintype "input"))
      (node (ref "RST") (pin "1") (pinfunction "1_1") (pintype "passive"))
    )
    (net (code "167") (name "~{S3.RESET}") (class "Default")
      (node (ref "C17") (pin "1") (pinfunction "1_1") (pintype "passive"))
      (node (ref "IC3") (pin "7") (pinfunction "~{RESET}_7") (pintype "input"))
      (node (ref "R20") (pin "1") (pinfunction "1_1") (pintype "passive"))
    )
  )
)
